# wifi-module.net
KiCad netlist of a schematic drawn in Altium Designer
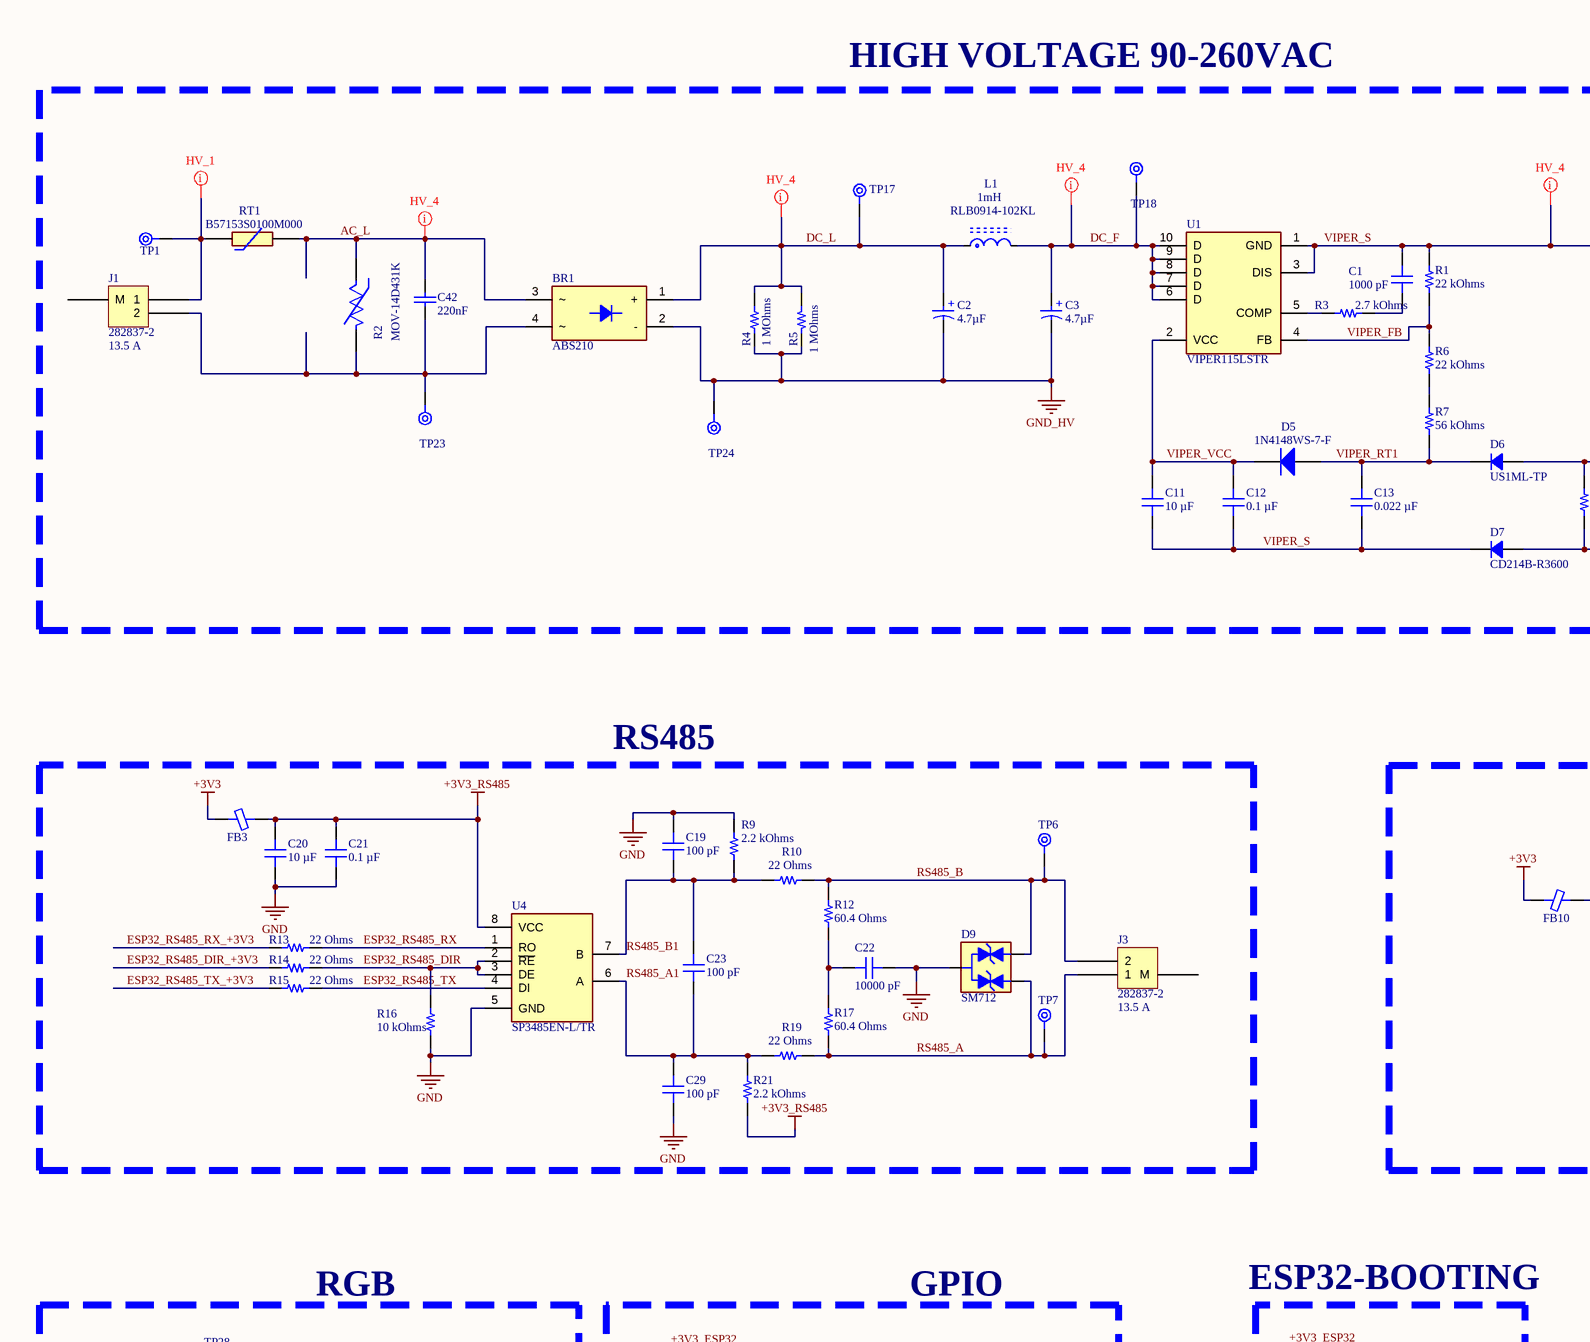
[diagram p0: wifi-module.SchDoc, top left]
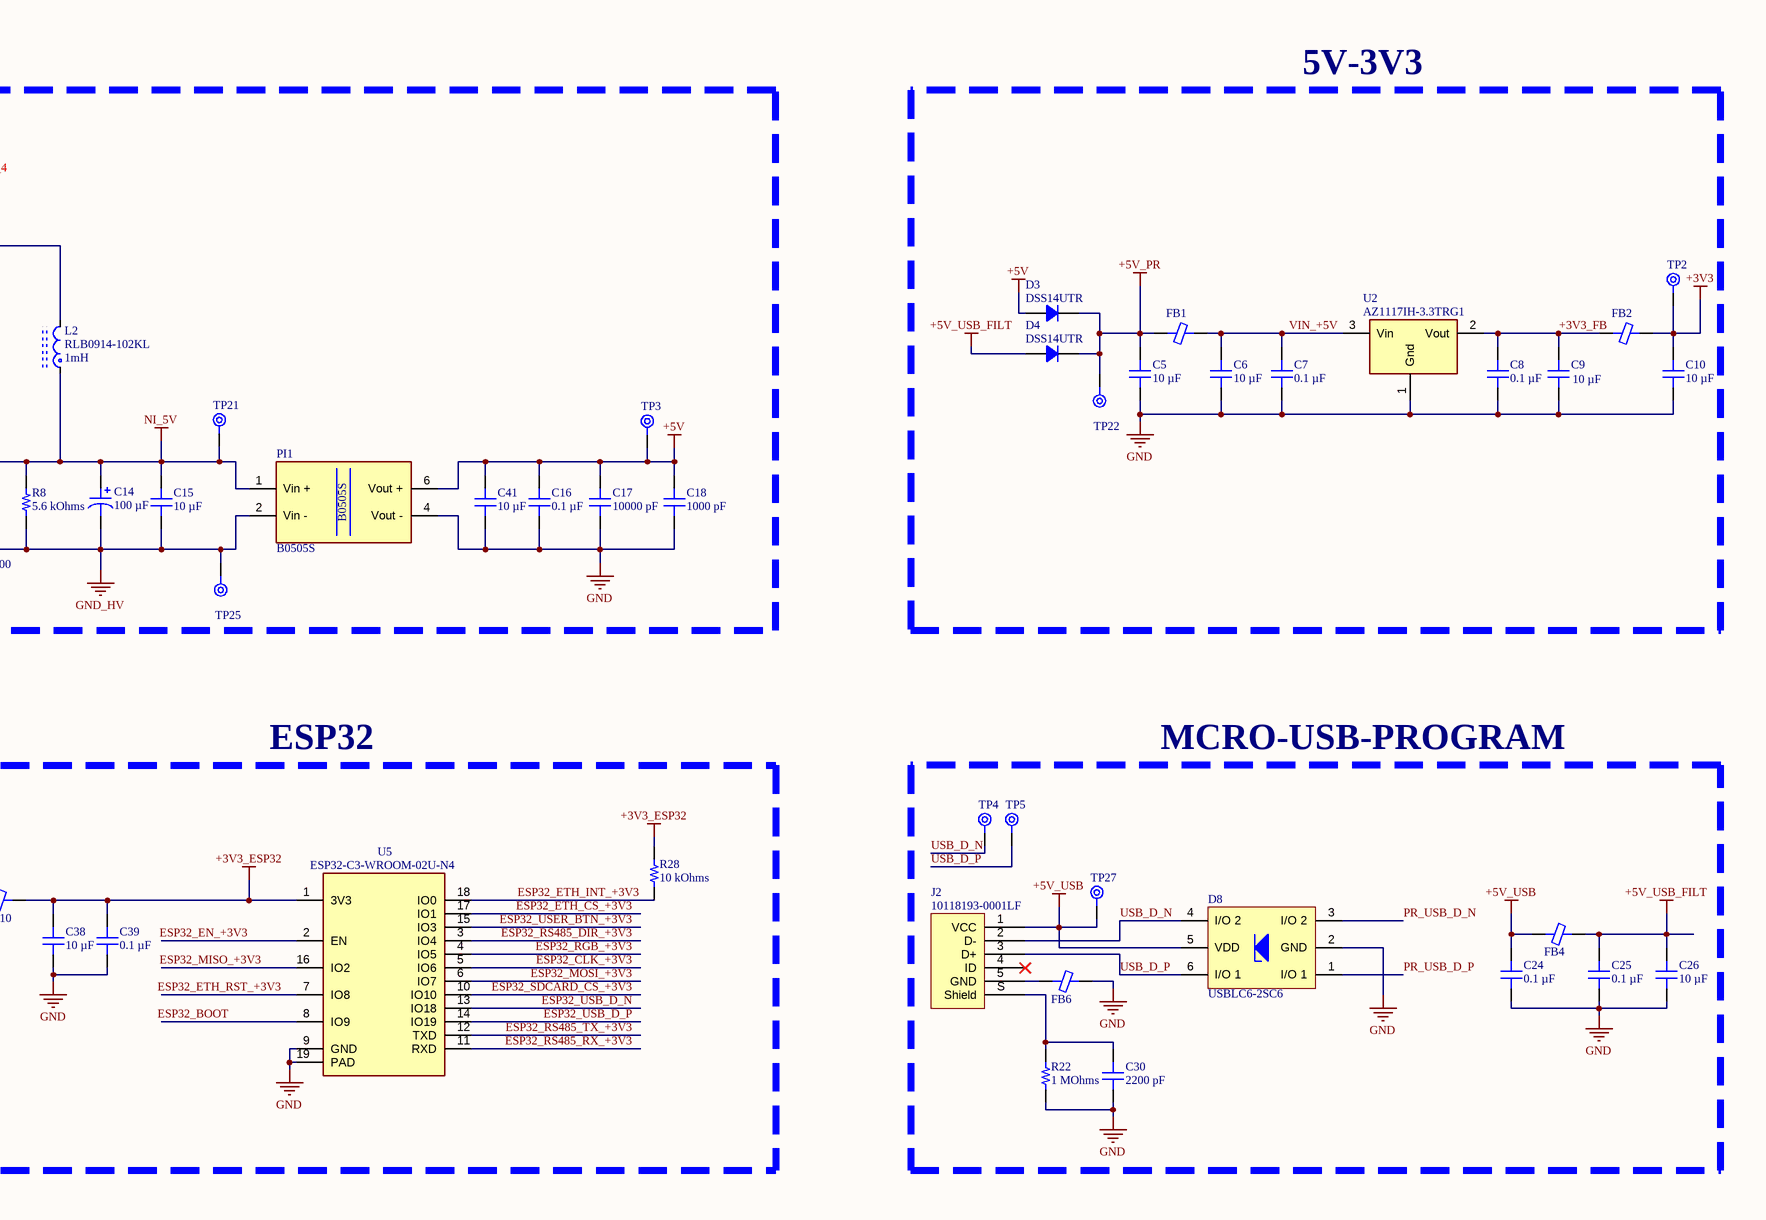
[diagram p1: wifi-module.SchDoc, top right]
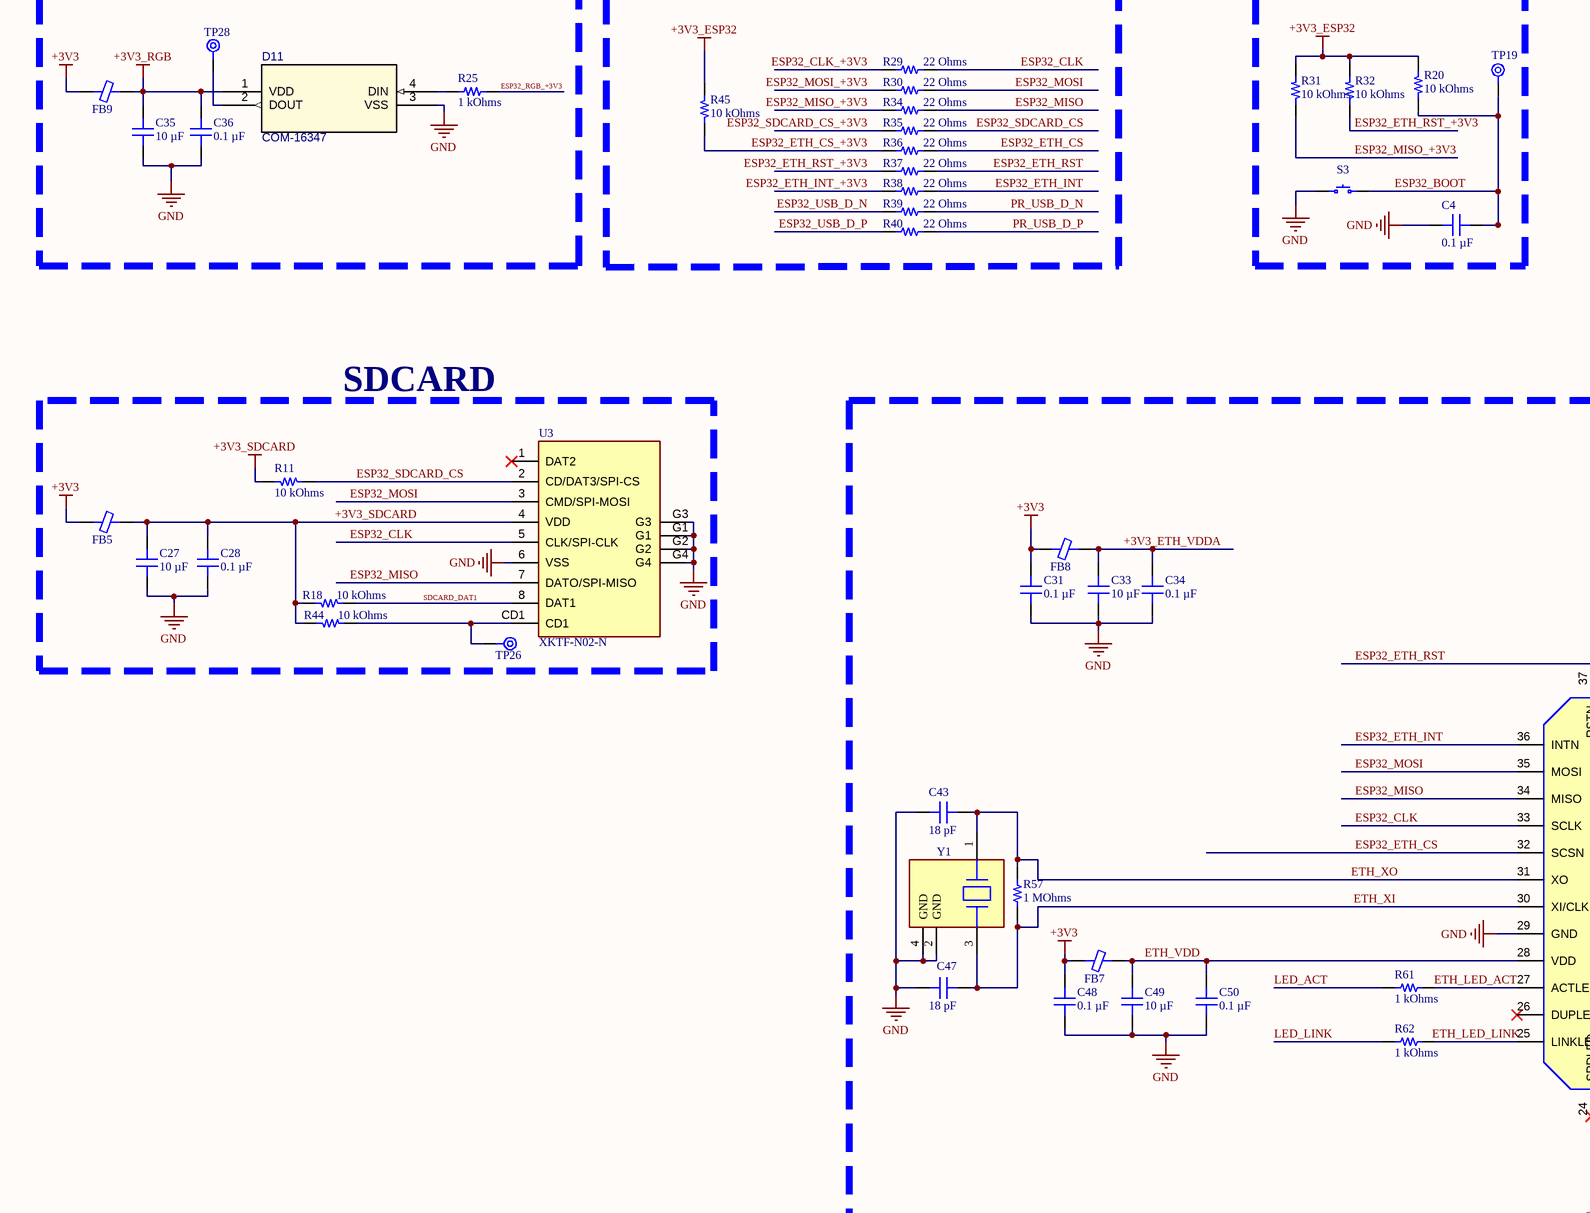
[diagram p2: wifi-module.SchDoc, bottom left]
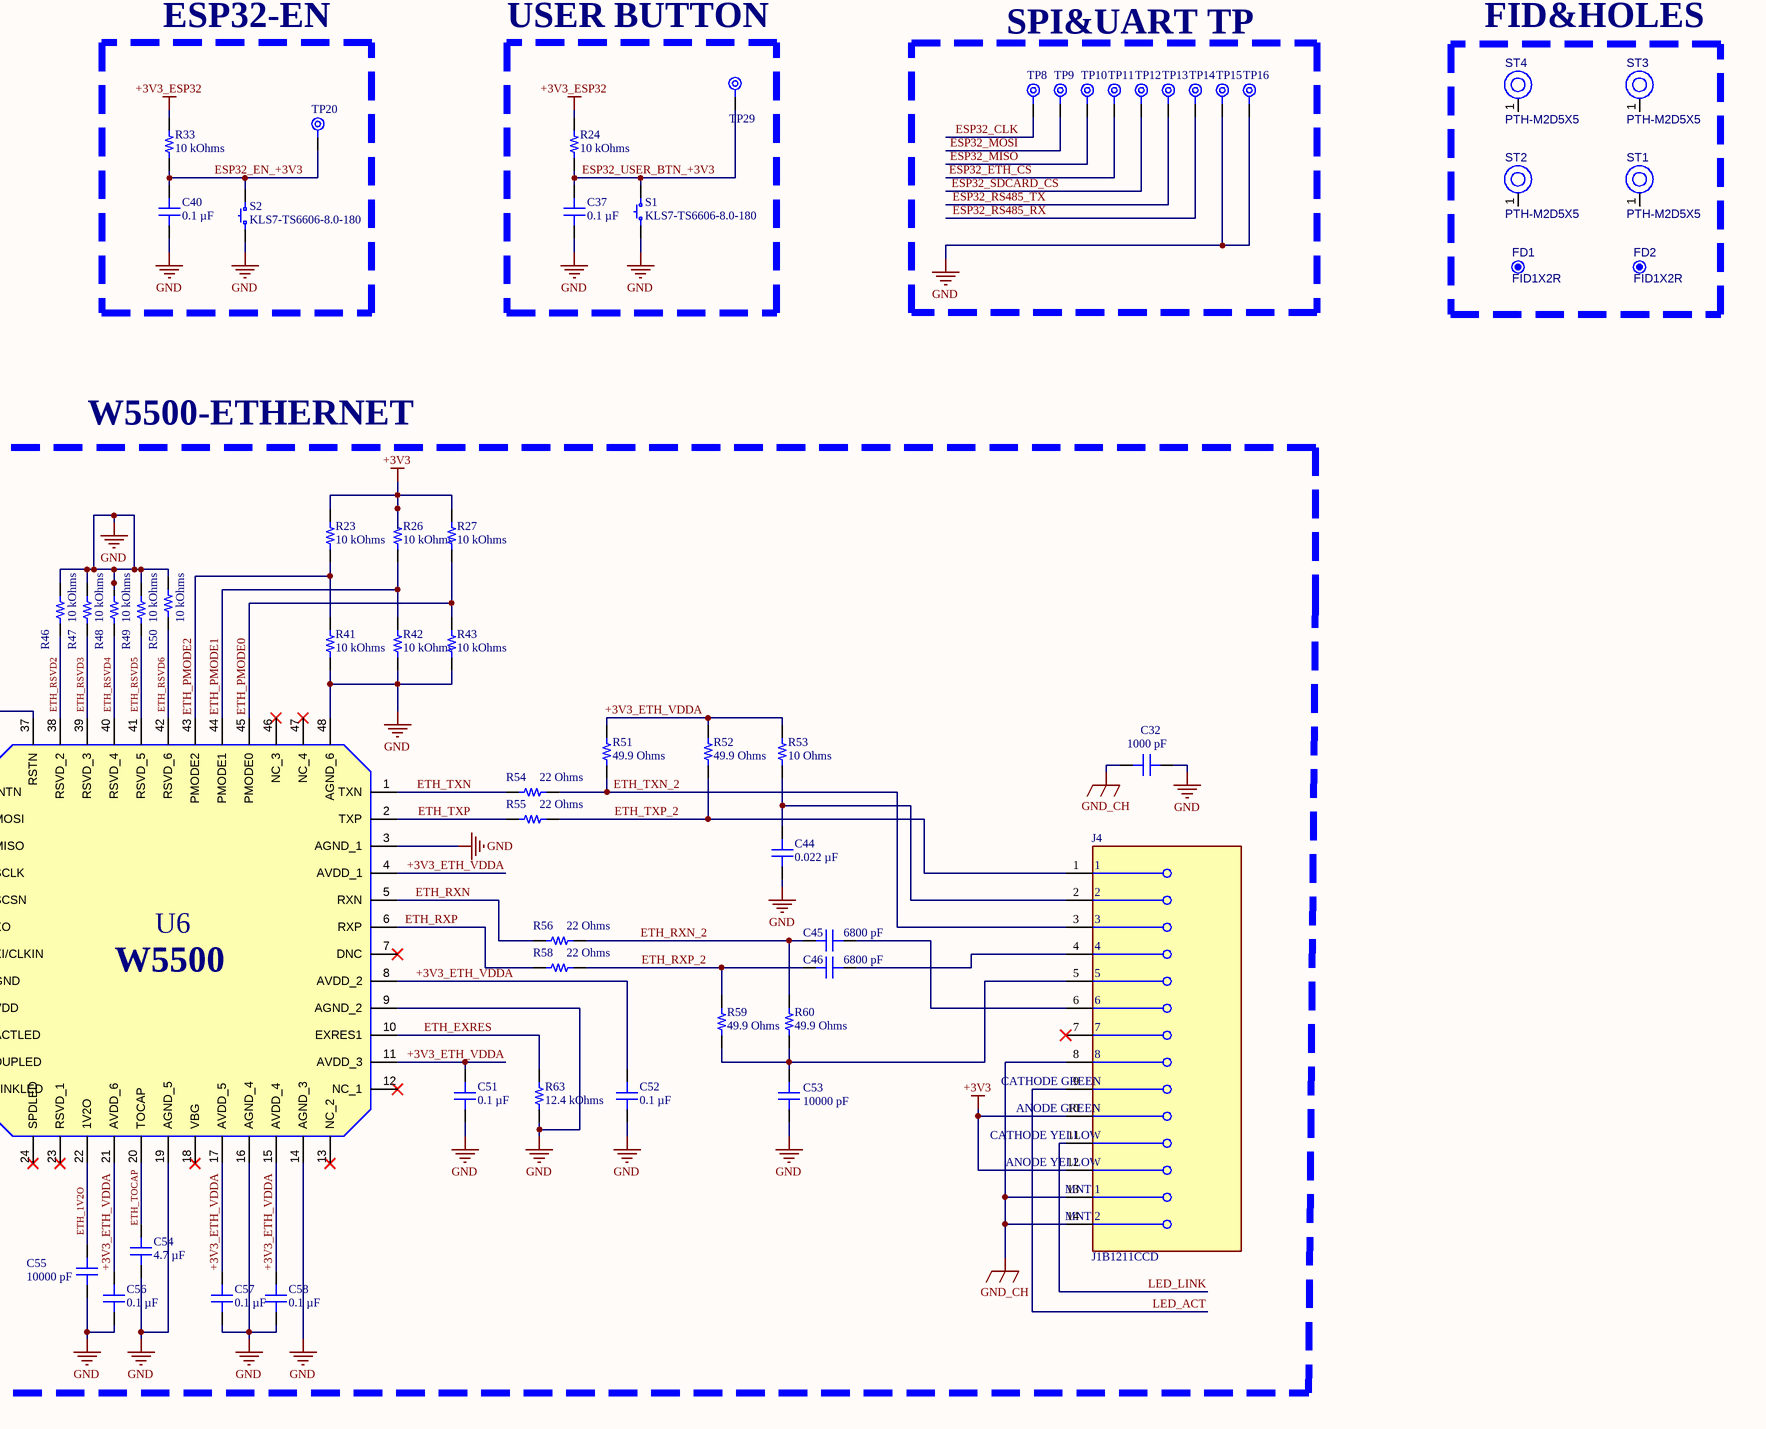
[diagram p3: wifi-module.SchDoc, bottom right]

(export (version "E")
  (design (tool "Eeschema 10.0.6"))
  (components
    (comp (ref "BR1")
      (value "ABS210")
      (footprint "SamacSys:SOP400P630X160-4N")
      (description "Bridge Rectifier")
      (libsource (lib "wifi-module-v02") (part "ABS210"))
    )
    (comp (ref "C1")
      (value "1000 pF")
      (footprint "CAP 0603_1608")
      (description "CAP CER 1000PF 50V X7R 0603")
      (fields (field (name "TOLERANCE") "±10%") (field (name "PART NUMBER") "C0603C102K5RACAUTO7411"))
      (libsource (lib "Dannie Main") (part "CAPACITOR"))
    )
    (comp (ref "C2")
      (value "4.7µF")
      (footprint "WCAP-ATG8_D8H11.5")
      (description "WCAP-ATG8 Aluminum Electrolytic Capacitor, Radial, THT, D8 x H11.5mm, 4.7uF, 400V")
      (fields
        (field (name "MANUFACTURER PART NUMBER") "860011374005")
        (field (name "MANUFACTURER") "Wurth Elektronik")
      )
      (libsource (lib "Dannie Main") (part "Capacitor_Polarized"))
    )
    (comp (ref "C3")
      (value "4.7µF")
      (footprint "WCAP-ATG8_D8H11.5")
      (description "WCAP-ATG8 Aluminum Electrolytic Capacitor, Radial, THT, D8 x H11.5mm, 4.7uF, 400V")
      (fields
        (field (name "MANUFACTURER PART NUMBER") "860011374005")
        (field (name "MANUFACTURER") "Wurth Elektronik")
      )
      (libsource (lib "Dannie Main") (part "Capacitor_Polarized"))
    )
    (comp (ref "C4")
      (value "0.1 µF")
      (footprint "CAP 0603_1608")
      (description "CAP CER 0.1UF 50V X7R 0603")
      (fields (field (name "MANUFACTURER") "Yageo") (field (name "PART NUMBER") "CC0603JRX7R9BB104"))
      (libsource (lib "Dannie Main") (part "CAPACITOR"))
    )
    (comp (ref "C5")
      (value "10 µF")
      (footprint "CAP 0805_2012")
      (description "CAP CER 10UF 25V X5R 0805")
      (fields
        (field (name "PART NUMBER") "CL21A106KAYNNNE")
        (field (name "MANUFACTURER") "Samsung Electro-Mechanics")
      )
      (libsource (lib "Dannie Main") (part "CAPACITOR"))
    )
    (comp (ref "C6")
      (value "10 µF")
      (footprint "CAP 0805_2012")
      (description "CAP CER 10UF 25V X5R 0805")
      (fields
        (field (name "PART NUMBER") "CL21A106KAYNNNE")
        (field (name "MANUFACTURER") "Samsung Electro-Mechanics")
      )
      (libsource (lib "Dannie Main") (part "CAPACITOR"))
    )
    (comp (ref "C7")
      (value "0.1 µF")
      (footprint "CAP 0603_1608")
      (description "CAP CER 0.1UF 50V X7R 0603")
      (fields (field (name "MANUFACTURER") "Yageo") (field (name "PART NUMBER") "CC0603JRX7R9BB104"))
      (libsource (lib "Dannie Main") (part "CAPACITOR"))
    )
    (comp (ref "C8")
      (value "0.1 µF")
      (footprint "CAP 0603_1608")
      (description "CAP CER 0.1UF 50V X7R 0603")
      (fields (field (name "MANUFACTURER") "Yageo") (field (name "PART NUMBER") "CC0603JRX7R9BB104"))
      (libsource (lib "Dannie Main") (part "CAPACITOR"))
    )
    (comp (ref "C9")
      (value "10 µF")
      (footprint "CAP 0805_2012")
      (description "CAP CER 10UF 25V X5R 0805")
      (fields
        (field (name "PART NUMBER") "CL21A106KAYNNNE")
        (field (name "MANUFACTURER") "Samsung Electro-Mechanics")
      )
      (libsource (lib "Dannie Main") (part "CAPACITOR"))
    )
    (comp (ref "C10")
      (value "10 µF")
      (footprint "CAP 0805_2012")
      (description "CAP CER 10UF 25V X5R 0805")
      (fields
        (field (name "PART NUMBER") "CL21A106KAYNNNE")
        (field (name "MANUFACTURER") "Samsung Electro-Mechanics")
      )
      (libsource (lib "Dannie Main") (part "CAPACITOR"))
    )
    (comp (ref "C11")
      (value "10 µF")
      (footprint "CAP 0805_2012")
      (description "CAP CER 10UF 25V X5R 0805")
      (fields
        (field (name "PART NUMBER") "CL21A106KAYNNNE")
        (field (name "MANUFACTURER") "Samsung Electro-Mechanics")
      )
      (libsource (lib "Dannie Main") (part "CAPACITOR"))
    )
    (comp (ref "C12")
      (value "0.1 µF")
      (footprint "CAP 0603_1608")
      (description "CAP CER 0.1UF 50V X7R 0603")
      (fields (field (name "MANUFACTURER") "Yageo") (field (name "PART NUMBER") "CC0603JRX7R9BB104"))
      (libsource (lib "Dannie Main") (part "CAPACITOR"))
    )
    (comp (ref "C13")
      (value "0.022 µF")
      (footprint "CAP 0603_1608")
      (description "CAP CER 0.022UF 50V X7R 0603")
      (fields (field (name "MANUFACTURER") "Samsung Electro-Mechanics") (field (name "TOLERANCE") "±10%"))
      (libsource (lib "Dannie Main") (part "CAPACITOR"))
    )
    (comp (ref "C14")
      (value "100 µF")
      (footprint "CAP ALSMD POLY 8.3MM H6.0MM")
      (description "CAP ALUM POLY 100UF 20% 35V SMD")
      (fields (field (name "MANUFACTURER") "KEMET") (field (name "TOLERANCE") "±20%"))
      (libsource (lib "Dannie Main") (part "POLARISED CAPACITOR"))
    )
    (comp (ref "C15")
      (value "10 µF")
      (footprint "CAP 0805_2012")
      (description "CAP CER 10UF 25V X5R 0805")
      (fields
        (field (name "PART NUMBER") "CL21A106KAYNNNE")
        (field (name "MANUFACTURER") "Samsung Electro-Mechanics")
      )
      (libsource (lib "Dannie Main") (part "CAPACITOR"))
    )
    (comp (ref "C16")
      (value "0.1 µF")
      (footprint "CAP 0603_1608")
      (description "CAP CER 0.1UF 50V X7R 0603")
      (fields (field (name "MANUFACTURER") "Yageo") (field (name "PART NUMBER") "CC0603JRX7R9BB104"))
      (libsource (lib "Dannie Main") (part "CAPACITOR"))
    )
    (comp (ref "C17")
      (value "10000 pF")
      (footprint "CAP 0603_1608")
      (description "CAP CER 10000PF 50V X7R 0603")
      (fields (field (name "TOLERANCE") "±10%") (field (name "PART NUMBER") "CL10B103KB8NNNC"))
      (libsource (lib "Dannie Main") (part "CAPACITOR"))
    )
    (comp (ref "C18")
      (value "1000 pF")
      (footprint "CAP 0603_1608")
      (description "CAP CER 1000PF 50V X7R 0603")
      (fields (field (name "TOLERANCE") "±10%") (field (name "PART NUMBER") "C0603C102K5RACAUTO7411"))
      (libsource (lib "Dannie Main") (part "CAPACITOR"))
    )
    (comp (ref "C19")
      (value "100 pF")
      (footprint "CAP 0603_1608")
      (description "CAP CER 100PF 50V C0G/NP0 0603")
      (fields (field (name "TOLERANCE") "±5%") (field (name "MANUFACTURER") "Samsung Electro-Mechanics"))
      (libsource (lib "Dannie Main") (part "CAPACITOR"))
    )
    (comp (ref "C20")
      (value "10 µF")
      (footprint "CAP 0603_1608")
      (description "CAP CER 10UF 6.3V X5R 0603")
      (fields (field (name "TOLERANCE") "±20%") (field (name "MANUFACTURER") "Samsung Electro-Mechanics"))
      (libsource (lib "Dannie Main") (part "CAPACITOR"))
    )
    (comp (ref "C21")
      (value "0.1 µF")
      (footprint "CAP 0603_1608")
      (description "CAP CER 0.1UF 50V X7R 0603")
      (fields (field (name "MANUFACTURER") "Yageo") (field (name "PART NUMBER") "CC0603JRX7R9BB104"))
      (libsource (lib "Dannie Main") (part "CAPACITOR"))
    )
    (comp (ref "C22")
      (value "10000 pF")
      (footprint "CAP 0603_1608")
      (description "CAP CER 10000PF 50V X7R 0603")
      (fields (field (name "TOLERANCE") "±10%") (field (name "PART NUMBER") "CL10B103KB8NNNC"))
      (libsource (lib "Dannie Main") (part "CAPACITOR"))
    )
    (comp (ref "C23")
      (value "100 pF")
      (footprint "CAP 0603_1608")
      (description "CAP CER 100PF 50V C0G/NP0 0603")
      (fields (field (name "TOLERANCE") "±5%") (field (name "MANUFACTURER") "Samsung Electro-Mechanics"))
      (libsource (lib "Dannie Main") (part "CAPACITOR"))
    )
    (comp (ref "C24")
      (value "0.1 µF")
      (footprint "CAP 0603_1608")
      (description "CAP CER 0.1UF 50V X7R 0603")
      (fields (field (name "MANUFACTURER") "Yageo") (field (name "PART NUMBER") "CC0603JRX7R9BB104"))
      (libsource (lib "Dannie Main") (part "CAPACITOR"))
    )
    (comp (ref "C25")
      (value "0.1 µF")
      (footprint "CAP 0603_1608")
      (description "CAP CER 0.1UF 50V X7R 0603")
      (fields (field (name "MANUFACTURER") "Yageo") (field (name "PART NUMBER") "CC0603JRX7R9BB104"))
      (libsource (lib "Dannie Main") (part "CAPACITOR"))
    )
    (comp (ref "C26")
      (value "10 µF")
      (footprint "CAP 0805_2012")
      (description "CAP CER 10UF 25V X5R 0805")
      (fields
        (field (name "PART NUMBER") "CL21A106KAYNNNE")
        (field (name "MANUFACTURER") "Samsung Electro-Mechanics")
      )
      (libsource (lib "Dannie Main") (part "CAPACITOR"))
    )
    (comp (ref "C27")
      (value "10 µF")
      (footprint "CAP 0603_1608")
      (description "CAP CER 10UF 6.3V X5R 0603")
      (fields (field (name "TOLERANCE") "±20%") (field (name "MANUFACTURER") "Samsung Electro-Mechanics"))
      (libsource (lib "Dannie Main") (part "CAPACITOR"))
    )
    (comp (ref "C28")
      (value "0.1 µF")
      (footprint "CAP 0603_1608")
      (description "CAP CER 0.1UF 50V X7R 0603")
      (fields (field (name "MANUFACTURER") "Yageo") (field (name "PART NUMBER") "CC0603JRX7R9BB104"))
      (libsource (lib "Dannie Main") (part "CAPACITOR"))
    )
    (comp (ref "C29")
      (value "100 pF")
      (footprint "CAP 0603_1608")
      (description "CAP CER 100PF 50V C0G/NP0 0603")
      (fields (field (name "TOLERANCE") "±5%") (field (name "MANUFACTURER") "Samsung Electro-Mechanics"))
      (libsource (lib "Dannie Main") (part "CAPACITOR"))
    )
    (comp (ref "C30")
      (value "2200 pF")
      (footprint "CAP 1206_3216 - 0.8MM")
      (description "CAP CER 2200PF 2KV X7R 1206")
      (fields (field (name "MANUFACTURER") "KEMET") (field (name "TOLERANCE") "±10%"))
      (libsource (lib "Dannie Main") (part "CAPACITOR"))
    )
    (comp (ref "C31")
      (value "0.1 µF")
      (footprint "CAP 0603_1608")
      (description "CAP CER 0.1UF 50V X7R 0603")
      (fields (field (name "MANUFACTURER") "Yageo") (field (name "PART NUMBER") "CC0603JRX7R9BB104"))
      (libsource (lib "Dannie Main") (part "CAPACITOR"))
    )
    (comp (ref "C32")
      (value "1000 pF")
      (footprint "CAP 1206_3216 - 0.8MM")
      (description "CAP CER 1000PF 2KV X7R 1206")
      (fields (field (name "TOLERANCE") "±10%") (field (name "MANUFACTURER") "Johanson Dielectrics Inc."))
      (libsource (lib "Dannie Main") (part "CAPACITOR"))
    )
    (comp (ref "C33")
      (value "10 µF")
      (footprint "CAP 0603_1608")
      (description "CAP CER 10UF 6.3V X5R 0603")
      (fields (field (name "TOLERANCE") "±20%") (field (name "MANUFACTURER") "Samsung Electro-Mechanics"))
      (libsource (lib "Dannie Main") (part "CAPACITOR"))
    )
    (comp (ref "C34")
      (value "0.1 µF")
      (footprint "CAP 0603_1608")
      (description "CAP CER 0.1UF 50V X7R 0603")
      (fields (field (name "MANUFACTURER") "Yageo") (field (name "PART NUMBER") "CC0603JRX7R9BB104"))
      (libsource (lib "Dannie Main") (part "CAPACITOR"))
    )
    (comp (ref "C35")
      (value "10 µF")
      (footprint "CAP 0603_1608")
      (description "CAP CER 10UF 6.3V X5R 0603")
      (fields (field (name "TOLERANCE") "±20%") (field (name "MANUFACTURER") "Samsung Electro-Mechanics"))
      (libsource (lib "Dannie Main") (part "CAPACITOR"))
    )
    (comp (ref "C36")
      (value "0.1 µF")
      (footprint "CAP 0603_1608")
      (description "CAP CER 0.1UF 50V X7R 0603")
      (fields (field (name "MANUFACTURER") "Yageo") (field (name "PART NUMBER") "CC0603JRX7R9BB104"))
      (libsource (lib "Dannie Main") (part "CAPACITOR"))
    )
    (comp (ref "C37")
      (value "0.1 µF")
      (footprint "CAP 0603_1608")
      (description "CAP CER 0.1UF 50V X7R 0603")
      (fields (field (name "MANUFACTURER") "Yageo") (field (name "PART NUMBER") "CC0603JRX7R9BB104"))
      (libsource (lib "Dannie Main") (part "CAPACITOR"))
    )
    (comp (ref "C38")
      (value "10 µF")
      (footprint "CAP 0603_1608")
      (description "CAP CER 10UF 6.3V X5R 0603")
      (fields (field (name "TOLERANCE") "±20%") (field (name "MANUFACTURER") "Samsung Electro-Mechanics"))
      (libsource (lib "Dannie Main") (part "CAPACITOR"))
    )
    (comp (ref "C39")
      (value "0.1 µF")
      (footprint "CAP 0603_1608")
      (description "CAP CER 0.1UF 50V X7R 0603")
      (fields (field (name "MANUFACTURER") "Yageo") (field (name "PART NUMBER") "CC0603JRX7R9BB104"))
      (libsource (lib "Dannie Main") (part "CAPACITOR"))
    )
    (comp (ref "C40")
      (value "0.1 µF")
      (footprint "CAP 0603_1608")
      (description "CAP CER 0.1UF 50V X7R 0603")
      (fields (field (name "MANUFACTURER") "Yageo") (field (name "PART NUMBER") "CC0603JRX7R9BB104"))
      (libsource (lib "Dannie Main") (part "CAPACITOR"))
    )
    (comp (ref "C41")
      (value "10 µF")
      (footprint "CAP 0805_2012")
      (description "CAP CER 10UF 25V X5R 0805")
      (fields
        (field (name "PART NUMBER") "CL21A106KAYNNNE")
        (field (name "MANUFACTURER") "Samsung Electro-Mechanics")
      )
      (libsource (lib "Dannie Main") (part "CAPACITOR"))
    )
    (comp (ref "C42")
      (value "220nF")
      (footprint "WCAP-FTX2_L15W7H12.5")
      (description "WCAP-FTX2 Film Capacitor, THT, L15 x W7 x H12.5mm, 220nF, 275V")
      (fields
        (field (name "MANUFACTURER") "Wurth Elektronik")
        (field (name "MANUFACTURER PART NUMBER") "890324024002")
      )
      (libsource (lib "Dannie Main") (part "Capacitor_Non-Polarized"))
    )
    (comp (ref "C43")
      (value "18 pF")
      (footprint "CAP 0603_1608")
      (description "CAP CER 0603 18PF 50V ULTRA STAB")
      (fields (field (name "PART NUMBER") "C0603C180K5HACAUTO") (field (name "MANUFACTURER") "KEMET"))
      (libsource (lib "Dannie Main") (part "CAPACITOR"))
    )
    (comp (ref "C44")
      (value "0.022 µF")
      (footprint "CAP 0603_1608")
      (description "CAP CER 0.022UF 50V X7R 0603")
      (fields (field (name "PART NUMBER") "C0603C223M5RACAUTO") (field (name "TOLERANCE") "±20%"))
      (libsource (lib "Dannie Main") (part "CAPACITOR"))
    )
    (comp (ref "C45")
      (value "6800 pF")
      (footprint "CAP 0603_1608")
      (description "CAP CER 6800PF 50V X7R 0603")
      (fields (field (name "PART NUMBER") "C0603C682K5RAC7411") (field (name "TOLERANCE") "±10%"))
      (libsource (lib "Dannie Main") (part "CAPACITOR"))
    )
    (comp (ref "C46")
      (value "6800 pF")
      (footprint "CAP 0603_1608")
      (description "CAP CER 6800PF 50V X7R 0603")
      (fields (field (name "PART NUMBER") "C0603C682K5RAC7411") (field (name "TOLERANCE") "±10%"))
      (libsource (lib "Dannie Main") (part "CAPACITOR"))
    )
    (comp (ref "C47")
      (value "18 pF")
      (footprint "CAP 0603_1608")
      (description "CAP CER 0603 18PF 50V ULTRA STAB")
      (fields (field (name "PART NUMBER") "C0603C180K5HACAUTO") (field (name "MANUFACTURER") "KEMET"))
      (libsource (lib "Dannie Main") (part "CAPACITOR"))
    )
    (comp (ref "C48")
      (value "0.1 µF")
      (footprint "CAP 0603_1608")
      (description "CAP CER 0.1UF 50V X7R 0603")
      (fields (field (name "MANUFACTURER") "Yageo") (field (name "PART NUMBER") "CC0603JRX7R9BB104"))
      (libsource (lib "Dannie Main") (part "CAPACITOR"))
    )
    (comp (ref "C49")
      (value "10 µF")
      (footprint "CAP 0603_1608")
      (description "CAP CER 10UF 6.3V X5R 0603")
      (fields (field (name "TOLERANCE") "±20%") (field (name "MANUFACTURER") "Samsung Electro-Mechanics"))
      (libsource (lib "Dannie Main") (part "CAPACITOR"))
    )
    (comp (ref "C50")
      (value "0.1 µF")
      (footprint "CAP 0603_1608")
      (description "CAP CER 0.1UF 50V X7R 0603")
      (fields (field (name "MANUFACTURER") "Yageo") (field (name "PART NUMBER") "CC0603JRX7R9BB104"))
      (libsource (lib "Dannie Main") (part "CAPACITOR"))
    )
    (comp (ref "C51")
      (value "0.1 µF")
      (footprint "CAP 0603_1608")
      (description "CAP CER 0.1UF 50V X7R 0603")
      (fields (field (name "MANUFACTURER") "Yageo") (field (name "PART NUMBER") "CC0603JRX7R9BB104"))
      (libsource (lib "Dannie Main") (part "CAPACITOR"))
    )
    (comp (ref "C52")
      (value "0.1 µF")
      (footprint "CAP 0603_1608")
      (description "CAP CER 0.1UF 50V X7R 0603")
      (fields (field (name "MANUFACTURER") "Yageo") (field (name "PART NUMBER") "CC0603JRX7R9BB104"))
      (libsource (lib "Dannie Main") (part "CAPACITOR"))
    )
    (comp (ref "C53")
      (value "10000 pF")
      (footprint "CAP 0603_1608")
      (description "CAP CER 10000PF 50V X7R 0603")
      (fields (field (name "TOLERANCE") "±10%") (field (name "PART NUMBER") "CL10B103KB8NNNC"))
      (libsource (lib "Dannie Main") (part "CAPACITOR"))
    )
    (comp (ref "C54")
      (value "4.7 µF")
      (footprint "CAP 1206_3216 - 0.8MM")
      (description "CAP CER 4.7UF 50V X7R 1206")
      (fields
        (field (name "PART NUMBER") "CL31B475KBHNNNE")
        (field (name "MANUFACTURER") "Samsung Electro-Mechanics")
      )
      (libsource (lib "Dannie Main") (part "CAPACITOR"))
    )
    (comp (ref "C55")
      (value "10000 pF")
      (footprint "CAP 0603_1608")
      (description "CAP CER 10000PF 50V X7R 0603")
      (fields (field (name "TOLERANCE") "±10%") (field (name "PART NUMBER") "CL10B103KB8NNNC"))
      (libsource (lib "Dannie Main") (part "CAPACITOR"))
    )
    (comp (ref "C56")
      (value "0.1 µF")
      (footprint "CAP 0603_1608")
      (description "CAP CER 0.1UF 50V X7R 0603")
      (fields (field (name "MANUFACTURER") "Yageo") (field (name "PART NUMBER") "CC0603JRX7R9BB104"))
      (libsource (lib "Dannie Main") (part "CAPACITOR"))
    )
    (comp (ref "C57")
      (value "0.1 µF")
      (footprint "CAP 0603_1608")
      (description "CAP CER 0.1UF 50V X7R 0603")
      (fields (field (name "MANUFACTURER") "Yageo") (field (name "PART NUMBER") "CC0603JRX7R9BB104"))
      (libsource (lib "Dannie Main") (part "CAPACITOR"))
    )
    (comp (ref "C58")
      (value "0.1 µF")
      (footprint "CAP 0603_1608")
      (description "CAP CER 0.1UF 50V X7R 0603")
      (fields (field (name "MANUFACTURER") "Yageo") (field (name "PART NUMBER") "CC0603JRX7R9BB104"))
      (libsource (lib "Dannie Main") (part "CAPACITOR"))
    )
    (comp (ref "D3")
      (value "DSS14UTR")
      (footprint "SOD123F")
      (description "SCHOTTKY 40V SOD-123FL")
      (fields (field (name "MANUFACTURER") "SMC Diode Solutions"))
      (libsource (lib "Dannie Main") (part "DIODE"))
    )
    (comp (ref "D4")
      (value "DSS14UTR")
      (footprint "SOD123F")
      (description "SCHOTTKY 40V SOD-123FL")
      (fields (field (name "MANUFACTURER") "SMC Diode Solutions"))
      (libsource (lib "Dannie Main") (part "DIODE"))
    )
    (comp (ref "D5")
      (value "1N4148WS-7-F")
      (footprint "DIOD-SOD323-2-A_V")
      (description "Fast Switching Diode, 75 V, 0.3 A, -65 to 150 degC, 2-Pin SOD323, RoHS, Tape and Reel")
      (fields (field (name "MANUFACTURER") "Diodes Inc"))
      (libsource (lib "Dannie Main") (part "D-AK-2"))
    )
    (comp (ref "D6")
      (value "US1ML-TP")
      (footprint "DO214AC SMA")
      (description "DIODE GEN PURP 1KV 1A DO214AC")
      (fields (field (name "MANUFACTURER") "Micro Commercial Co"))
      (libsource (lib "Dannie Main") (part "DIODE"))
    )
    (comp (ref "D7")
      (value "CD214B-R3600")
      (footprint "DO214AA SMB")
      (description "DIODE GEN PURP 600V 3A SMB")
      (fields (field (name "MANUFACTURER") "Bourns Inc."))
      (libsource (lib "Dannie Main") (part "DIODE"))
    )
    (comp (ref "D8")
      (value "USBLC6-2SC6")
      (footprint "STM-SOT23-6L_V")
      (description "Trans Voltage Suppressor Diode, 5V V(RWM), Unidirectional, 1 Element, Silicon")
      (libsource (lib "Dannie Main") (part "USBLC6-2SC6"))
    )
    (comp (ref "D9")
      (value "SM712")
      (footprint "SOT-23-3")
      (description "26V, 12V Clamp 17A (8/20µs) Ipp Tvs Diode Surface Mount SOT-23-3")
      (libsource (lib "Dannie Main") (part "SM712"))
    )
    (comp (ref "D11")
      (value "COM-16347")
      (footprint "COM-16347-Footprint-1")
      (description "Addressable Lighting - LED Serial NRZ (Shift Register) Red, Green, Blue (RGB)")
      (libsource (lib "Dannie Main") (part "COM-16347"))
    )
    (comp (ref "FB1")
      (value "MPZ1608S101ATAH0")
      (footprint "FER 0603_1608")
      (description "FERRITE BEAD 100 OHM 0603 1LN")
      (fields (field (name "MANUFACTURER") "TDK Corporation"))
      (libsource (lib "Dannie Main") (part "FERRITE CHIP"))
    )
    (comp (ref "FB2")
      (value "MPZ1608S101ATAH0")
      (footprint "FER 0603_1608")
      (description "FERRITE BEAD 100 OHM 0603 1LN")
      (fields (field (name "MANUFACTURER") "TDK Corporation"))
      (libsource (lib "Dannie Main") (part "FERRITE CHIP"))
    )
    (comp (ref "FB3")
      (value "MPZ1608S101ATAH0")
      (footprint "FER 0603_1608")
      (description "FERRITE BEAD 100 OHM 0603 1LN")
      (fields (field (name "MANUFACTURER") "TDK Corporation"))
      (libsource (lib "Dannie Main") (part "FERRITE CHIP"))
    )
    (comp (ref "FB4")
      (value "MPZ1608S101ATAH0")
      (footprint "FER 0603_1608")
      (description "FERRITE BEAD 100 OHM 0603 1LN")
      (fields (field (name "MANUFACTURER") "TDK Corporation"))
      (libsource (lib "Dannie Main") (part "FERRITE CHIP"))
    )
    (comp (ref "FB5")
      (value "MPZ1608S101ATAH0")
      (footprint "FER 0603_1608")
      (description "FERRITE BEAD 100 OHM 0603 1LN")
      (fields (field (name "MANUFACTURER") "TDK Corporation"))
      (libsource (lib "Dannie Main") (part "FERRITE CHIP"))
    )
    (comp (ref "FB6")
      (value "MPZ1608S101ATAH0")
      (footprint "FER 0603_1608")
      (description "FERRITE BEAD 100 OHM 0603 1LN")
      (fields (field (name "MANUFACTURER") "TDK Corporation"))
      (libsource (lib "Dannie Main") (part "FERRITE CHIP"))
    )
    (comp (ref "FB7")
      (value "MPZ1608S101ATAH0")
      (footprint "FER 0603_1608")
      (description "FERRITE BEAD 100 OHM 0603 1LN")
      (fields (field (name "MANUFACTURER") "TDK Corporation"))
      (libsource (lib "Dannie Main") (part "FERRITE CHIP"))
    )
    (comp (ref "FB8")
      (value "MPZ1608S101ATAH0")
      (footprint "FER 0603_1608")
      (description "FERRITE BEAD 100 OHM 0603 1LN")
      (fields (field (name "MANUFACTURER") "TDK Corporation"))
      (libsource (lib "Dannie Main") (part "FERRITE CHIP"))
    )
    (comp (ref "FB9")
      (value "MPZ1608S101ATAH0")
      (footprint "FER 0603_1608")
      (description "FERRITE BEAD 100 OHM 0603 1LN")
      (fields (field (name "MANUFACTURER") "TDK Corporation"))
      (libsource (lib "Dannie Main") (part "FERRITE CHIP"))
    )
    (comp (ref "FB10")
      (value "MPZ1608S101ATAH0")
      (footprint "FER 0603_1608")
      (description "FERRITE BEAD 100 OHM 0603 1LN")
      (fields (field (name "MANUFACTURER") "TDK Corporation"))
      (libsource (lib "Dannie Main") (part "FERRITE CHIP"))
    )
    (comp (ref "FD1")
      (value "FID1X2R")
      (footprint "FID1X2R")
      (description "Fiducial - Round 1x2mm")
      (libsource (lib "Dannie Main") (part "CMP-00134-2"))
    )
    (comp (ref "FD2")
      (value "FID1X2R")
      (footprint "FID1X2R")
      (description "Fiducial - Round 1x2mm")
      (libsource (lib "Dannie Main") (part "CMP-00134-2"))
    )
    (comp (ref "J1")
      (value "282837-2")
      (footprint "TE 282837-2")
      (description "TERM BLK 2P SIDE ENT 5.08MM PCB")
      (fields
        (field (name "VOLTAGE") "300 V")
        (field (name "CURRENT") "13.5 A")
        (field (name "MANUFACTURER") "TE Connectivity AMP Connectors")
      )
      (libsource (lib "") (part "2 PIN_1"))
    )
    (comp (ref "J2")
      (value "10118193-0001LF")
      (footprint "FCI USB 10118193-0001LF")
      (description "CONN RCPT USB2.0 MICRO B SMD R/A")
      (fields (field (name "MANUFACTURER") "Amphenol ICC (FCI)"))
      (libsource (lib "Dannie Main") (part "USB 2.0 TYPE B MICRO"))
    )
    (comp (ref "J3")
      (value "282837-2")
      (footprint "TE 282837-2")
      (description "TERM BLK 2P SIDE ENT 5.08MM PCB")
      (fields
        (field (name "VOLTAGE") "300 V")
        (field (name "CURRENT") "13.5 A")
        (field (name "MANUFACTURER") "TE Connectivity AMP Connectors")
      )
      (libsource (lib "Dannie Main") (part "2 PIN"))
    )
    (comp (ref "J4")
      (value "J1B1211CCD")
      (footprint "FP-J1B1211CCD-MFG")
      (description "CONN JACK 1PORT 100 BASE-T PCB")
      (libsource (lib "Altium Content Vault") (part "043a9053fb366fe6dc2bf5dbfb72c80"))
    )
    (comp (ref "L1")
      (value "RLB0914-102KL")
      (footprint "FP-RLB0914-MFG")
      (description "FIXED IND 1MH 420MA 2.1 OHM TH")
      (fields (field (name "INDUCTANCE") "1mH") (field (name "TOLERANCE") "10%"))
      (libsource (lib "Altium Content Vault") (part "6087e8490c250d489263be6a42f1ae3"))
    )
    (comp (ref "L2")
      (value "RLB0914-102KL")
      (footprint "FP-RLB0914-MFG")
      (description "FIXED IND 1MH 420MA 2.1 OHM TH")
      (fields (field (name "INDUCTANCE") "1mH") (field (name "TOLERANCE") "10%"))
      (libsource (lib "Altium Content Vault") (part "6087e8490c250d489263be6a42f1ae3"))
    )
    (comp (ref "PI1")
      (value "B0505S")
      (footprint "wifi-module:B0505S")
      (description "Isolated Power Modules")
      (fields (field (name "MANUFACTURER_PART_NUMBER") "B0505S-2WR3"))
      (libsource (lib "wifi-module-v02") (part "B0505S-2WR3"))
    )
    (comp (ref "R1")
      (value "22 kOhms")
      (footprint "RES 0603_1608")
      (description "RES 22K OHM 1% 1/10W 0603")
      (fields (field (name "PART NUMBER") "RC0603FR-0722KL") (field (name "MANUFACTURER") "Yageo"))
      (libsource (lib "Dannie Main") (part "RESISTOR"))
    )
    (comp (ref "R2")
      (value "MOV-14D431K")
      (footprint "FP-MOV-14D431K-MFG")
      (description "VARISTOR 430V 4.5KA DISC 14MM")
      (fields
        (field (name "MANUFACTURER") "Bourns Inc.")
        (field (name "OCTOPART") "https://octopart.com/mov-14d431k-bourns-21388914")
      )
      (libsource (lib "Altium Content Vault") (part "78a88060d5b7b043d6e48adc4284376"))
    )
    (comp (ref "R3")
      (value "2.7 kOhms")
      (footprint "RES 0603_1608")
      (description "RES 2.7K OHM 1% 1/10W 0603")
      (fields (field (name "MANUFACTURER") "Yageo") (field (name "PART NUMBER") "RC0603FR-072K7L"))
      (libsource (lib "Dannie Main") (part "RESISTOR"))
    )
    (comp (ref "R4")
      (value "1 MOhms")
      (footprint "RES 2512_6432")
      (description "RES 1M OHM 5% 1W 2512")
      (fields (field (name "PART NUMBER") "RMCF2512JT1M00") (field (name "TOLERANCE") "±5%"))
      (libsource (lib "Dannie Main") (part "RESISTOR"))
    )
    (comp (ref "R5")
      (value "1 MOhms")
      (footprint "RES 2512_6432")
      (description "RES 1M OHM 5% 1W 2512")
      (fields (field (name "PART NUMBER") "RMCF2512JT1M00") (field (name "TOLERANCE") "±5%"))
      (libsource (lib "Dannie Main") (part "RESISTOR"))
    )
    (comp (ref "R6")
      (value "22 kOhms")
      (footprint "RES 0603_1608")
      (description "RES 22K OHM 1% 1/10W 0603")
      (fields (field (name "PART NUMBER") "RC0603FR-0722KL") (field (name "MANUFACTURER") "Yageo"))
      (libsource (lib "Dannie Main") (part "RESISTOR"))
    )
    (comp (ref "R7")
      (value "56 kOhms")
      (footprint "RES 0603_1608")
      (description "RES 56K OHM 1% 1/10W 0603")
      (fields (field (name "MANUFACTURER") "Yageo") (field (name "PART NUMBER") "RC0603FR-0756KL"))
      (libsource (lib "Dannie Main") (part "RESISTOR"))
    )
    (comp (ref "R8")
      (value "5.6 kOhms")
      (footprint "RES 0603_1608")
      (description "RES 5.6K OHM 1% 1/10W 0603")
      (fields (field (name "TOLERANCE") "±1%") (field (name "MANUFACTURER") "Yageo"))
      (libsource (lib "Dannie Main") (part "RESISTOR"))
    )
    (comp (ref "R9")
      (value "2.2 kOhms")
      (footprint "RES 0603_1608")
      (description "RES 2.2K OHM 1% 1/10W 0603")
      (fields (field (name "TOLERANCE") "±1%") (field (name "PART NUMBER") "RC0603FR-072K2L"))
      (libsource (lib "Dannie Main") (part "RESISTOR"))
    )
    (comp (ref "R10")
      (value "22 Ohms")
      (footprint "RES 0603_1608")
      (description "RES 22 OHM 1% 1/10W 0603")
      (fields (field (name "MANUFACTURER") "Yageo") (field (name "TOLERANCE") "±1%"))
      (libsource (lib "Dannie Main") (part "RESISTOR"))
    )
    (comp (ref "R11")
      (value "10 kOhms")
      (footprint "RES 0603_1608")
      (description "RES 10K OHM 1% 1/10W 0603")
      (fields (field (name "PART NUMBER") "RC0603FR-0710KL") (field (name "TOLERANCE") "±1%"))
      (libsource (lib "Dannie Main") (part "RESISTOR"))
    )
    (comp (ref "R12")
      (value "60.4 Ohms")
      (footprint "RES 0603_1608")
      (description "RES 60.4 OHM 1% 1/10W 0603")
      (fields (field (name "TOLERANCE") "±1%") (field (name "MANUFACTURER") "Yageo"))
      (libsource (lib "Dannie Main") (part "RESISTOR"))
    )
    (comp (ref "R13")
      (value "22 Ohms")
      (footprint "RES 0603_1608")
      (description "RES 22 OHM 1% 1/10W 0603")
      (fields (field (name "MANUFACTURER") "Yageo") (field (name "TOLERANCE") "±1%"))
      (libsource (lib "Dannie Main") (part "RESISTOR"))
    )
    (comp (ref "R14")
      (value "22 Ohms")
      (footprint "RES 0603_1608")
      (description "RES 22 OHM 1% 1/10W 0603")
      (fields (field (name "MANUFACTURER") "Yageo") (field (name "TOLERANCE") "±1%"))
      (libsource (lib "Dannie Main") (part "RESISTOR"))
    )
    (comp (ref "R15")
      (value "22 Ohms")
      (footprint "RES 0603_1608")
      (description "RES 22 OHM 1% 1/10W 0603")
      (fields (field (name "MANUFACTURER") "Yageo") (field (name "TOLERANCE") "±1%"))
      (libsource (lib "Dannie Main") (part "RESISTOR"))
    )
    (comp (ref "R16")
      (value "10 kOhms")
      (footprint "RES 0603_1608")
      (description "RES 10K OHM 1% 1/10W 0603")
      (fields (field (name "PART NUMBER") "RC0603FR-0710KL") (field (name "TOLERANCE") "±1%"))
      (libsource (lib "Dannie Main") (part "RESISTOR"))
    )
    (comp (ref "R17")
      (value "60.4 Ohms")
      (footprint "RES 0603_1608")
      (description "RES 60.4 OHM 1% 1/10W 0603")
      (fields (field (name "TOLERANCE") "±1%") (field (name "MANUFACTURER") "Yageo"))
      (libsource (lib "Dannie Main") (part "RESISTOR"))
    )
    (comp (ref "R18")
      (value "10 kOhms")
      (footprint "RES 0603_1608")
      (description "RES 10K OHM 1% 1/10W 0603")
      (fields (field (name "PART NUMBER") "RC0603FR-0710KL") (field (name "TOLERANCE") "±1%"))
      (libsource (lib "Dannie Main") (part "RESISTOR"))
    )
    (comp (ref "R19")
      (value "22 Ohms")
      (footprint "RES 0603_1608")
      (description "RES 22 OHM 1% 1/10W 0603")
      (fields (field (name "MANUFACTURER") "Yageo") (field (name "TOLERANCE") "±1%"))
      (libsource (lib "Dannie Main") (part "RESISTOR"))
    )
    (comp (ref "R20")
      (value "10 kOhms")
      (footprint "RES 0603_1608")
      (description "RES 10K OHM 1% 1/10W 0603")
      (fields (field (name "PART NUMBER") "RC0603FR-0710KL") (field (name "TOLERANCE") "±1%"))
      (libsource (lib "Dannie Main") (part "RESISTOR"))
    )
    (comp (ref "R21")
      (value "2.2 kOhms")
      (footprint "RES 0603_1608")
      (description "RES 2.2K OHM 1% 1/10W 0603")
      (fields (field (name "TOLERANCE") "±1%") (field (name "PART NUMBER") "RC0603FR-072K2L"))
      (libsource (lib "Dannie Main") (part "RESISTOR"))
    )
    (comp (ref "R22")
      (value "1 MOhms")
      (footprint "RES 1206_3216")
      (description "RES 1M OHM 1% 1/4W 1206")
      (fields (field (name "TOLERANCE") "±1%") (field (name "PART NUMBER") "RC1206FR-071ML"))
      (libsource (lib "Dannie Main") (part "RESISTOR"))
    )
    (comp (ref "R23")
      (value "10 kOhms")
      (footprint "RES 0603_1608")
      (description "RES 10K OHM 1% 1/10W 0603")
      (fields (field (name "PART NUMBER") "RC0603FR-0710KL") (field (name "TOLERANCE") "±1%"))
      (libsource (lib "Dannie Main") (part "RESISTOR"))
    )
    (comp (ref "R24")
      (value "10 kOhms")
      (footprint "RES 0603_1608")
      (description "RES 10K OHM 1% 1/10W 0603")
      (fields (field (name "PART NUMBER") "RC0603FR-0710KL") (field (name "TOLERANCE") "±1%"))
      (libsource (lib "Dannie Main") (part "RESISTOR"))
    )
    (comp (ref "R25")
      (value "1 kOhms")
      (footprint "RES 0603_1608")
      (description "RES 1K OHM 1% 1/10W 0603")
      (fields (field (name "PART NUMBER") "RC0603FR-071KL") (field (name "TOLERANCE") "±1%"))
      (libsource (lib "Dannie Main") (part "RESISTOR"))
    )
    (comp (ref "R26")
      (value "10 kOhms")
      (footprint "RES 0603_1608")
      (description "RES 10K OHM 1% 1/10W 0603")
      (fields (field (name "PART NUMBER") "RC0603FR-0710KL") (field (name "TOLERANCE") "±1%"))
      (libsource (lib "Dannie Main") (part "RESISTOR"))
    )
    (comp (ref "R27")
      (value "10 kOhms")
      (footprint "RES 0603_1608")
      (description "RES 10K OHM 1% 1/10W 0603")
      (fields (field (name "PART NUMBER") "RC0603FR-0710KL") (field (name "TOLERANCE") "±1%"))
      (libsource (lib "Dannie Main") (part "RESISTOR"))
    )
    (comp (ref "R28")
      (value "10 kOhms")
      (footprint "RES 0603_1608")
      (description "RES 10K OHM 1% 1/10W 0603")
      (fields (field (name "PART NUMBER") "RC0603FR-0710KL") (field (name "TOLERANCE") "±1%"))
      (libsource (lib "Dannie Main") (part "RESISTOR"))
    )
    (comp (ref "R29")
      (value "22 Ohms")
      (footprint "RES 0603_1608")
      (description "RES 22 OHM 1% 1/10W 0603")
      (fields (field (name "MANUFACTURER") "Yageo") (field (name "TOLERANCE") "±1%"))
      (libsource (lib "Dannie Main") (part "RESISTOR"))
    )
    (comp (ref "R30")
      (value "22 Ohms")
      (footprint "RES 0603_1608")
      (description "RES 22 OHM 1% 1/10W 0603")
      (fields (field (name "MANUFACTURER") "Yageo") (field (name "TOLERANCE") "±1%"))
      (libsource (lib "Dannie Main") (part "RESISTOR"))
    )
    (comp (ref "R31")
      (value "10 kOhms")
      (footprint "RES 0603_1608")
      (description "RES 10K OHM 1% 1/10W 0603")
      (fields (field (name "PART NUMBER") "RC0603FR-0710KL") (field (name "TOLERANCE") "±1%"))
      (libsource (lib "Dannie Main") (part "RESISTOR"))
    )
    (comp (ref "R32")
      (value "10 kOhms")
      (footprint "RES 0603_1608")
      (description "RES 10K OHM 1% 1/10W 0603")
      (fields (field (name "PART NUMBER") "RC0603FR-0710KL") (field (name "TOLERANCE") "±1%"))
      (libsource (lib "Dannie Main") (part "RESISTOR"))
    )
    (comp (ref "R33")
      (value "10 kOhms")
      (footprint "RES 0603_1608")
      (description "RES 10K OHM 1% 1/10W 0603")
      (fields (field (name "PART NUMBER") "RC0603FR-0710KL") (field (name "TOLERANCE") "±1%"))
      (libsource (lib "Dannie Main") (part "RESISTOR"))
    )
    (comp (ref "R34")
      (value "22 Ohms")
      (footprint "RES 0603_1608")
      (description "RES 22 OHM 1% 1/10W 0603")
      (fields (field (name "MANUFACTURER") "Yageo") (field (name "TOLERANCE") "±1%"))
      (libsource (lib "Dannie Main") (part "RESISTOR"))
    )
    (comp (ref "R35")
      (value "22 Ohms")
      (footprint "RES 0603_1608")
      (description "RES 22 OHM 1% 1/10W 0603")
      (fields (field (name "MANUFACTURER") "Yageo") (field (name "TOLERANCE") "±1%"))
      (libsource (lib "Dannie Main") (part "RESISTOR"))
    )
    (comp (ref "R36")
      (value "22 Ohms")
      (footprint "RES 0603_1608")
      (description "RES 22 OHM 1% 1/10W 0603")
      (fields (field (name "MANUFACTURER") "Yageo") (field (name "TOLERANCE") "±1%"))
      (libsource (lib "Dannie Main") (part "RESISTOR"))
    )
    (comp (ref "R37")
      (value "22 Ohms")
      (footprint "RES 0603_1608")
      (description "RES 22 OHM 1% 1/10W 0603")
      (fields (field (name "MANUFACTURER") "Yageo") (field (name "TOLERANCE") "±1%"))
      (libsource (lib "Dannie Main") (part "RESISTOR"))
    )
    (comp (ref "R38")
      (value "22 Ohms")
      (footprint "RES 0603_1608")
      (description "RES 22 OHM 1% 1/10W 0603")
      (fields (field (name "MANUFACTURER") "Yageo") (field (name "TOLERANCE") "±1%"))
      (libsource (lib "Dannie Main") (part "RESISTOR"))
    )
    (comp (ref "R39")
      (value "22 Ohms")
      (footprint "RES 0603_1608")
      (description "RES 22 OHM 1% 1/10W 0603")
      (fields (field (name "MANUFACTURER") "Yageo") (field (name "TOLERANCE") "±1%"))
      (libsource (lib "Dannie Main") (part "RESISTOR"))
    )
    (comp (ref "R40")
      (value "22 Ohms")
      (footprint "RES 0603_1608")
      (description "RES 22 OHM 1% 1/10W 0603")
      (fields (field (name "MANUFACTURER") "Yageo") (field (name "TOLERANCE") "±1%"))
      (libsource (lib "Dannie Main") (part "RESISTOR"))
    )
    (comp (ref "R41")
      (value "10 kOhms")
      (footprint "RES 0603_1608")
      (description "RES 10K OHM 1% 1/10W 0603")
      (fields (field (name "PART NUMBER") "RC0603FR-0710KL") (field (name "TOLERANCE") "±1%"))
      (libsource (lib "Dannie Main") (part "RESISTOR"))
    )
    (comp (ref "R42")
      (value "10 kOhms")
      (footprint "RES 0603_1608")
      (description "RES 10K OHM 1% 1/10W 0603")
      (fields (field (name "PART NUMBER") "RC0603FR-0710KL") (field (name "TOLERANCE") "±1%"))
      (libsource (lib "Dannie Main") (part "RESISTOR"))
    )
    (comp (ref "R43")
      (value "10 kOhms")
      (footprint "RES 0603_1608")
      (description "RES 10K OHM 1% 1/10W 0603")
      (fields (field (name "PART NUMBER") "RC0603FR-0710KL") (field (name "TOLERANCE") "±1%"))
      (libsource (lib "Dannie Main") (part "RESISTOR"))
    )
    (comp (ref "R44")
      (value "10 kOhms")
      (footprint "RES 0603_1608")
      (description "RES 10K OHM 1% 1/10W 0603")
      (fields (field (name "PART NUMBER") "RC0603FR-0710KL") (field (name "TOLERANCE") "±1%"))
      (libsource (lib "Dannie Main") (part "RESISTOR"))
    )
    (comp (ref "R45")
      (value "10 kOhms")
      (footprint "RES 0603_1608")
      (description "RES 10K OHM 1% 1/10W 0603")
      (fields (field (name "PART NUMBER") "RC0603FR-0710KL") (field (name "TOLERANCE") "±1%"))
      (libsource (lib "Dannie Main") (part "RESISTOR"))
    )
    (comp (ref "R46")
      (value "10 kOhms")
      (footprint "RES 0603_1608")
      (description "RES 10K OHM 1% 1/10W 0603")
      (fields (field (name "PART NUMBER") "RC0603FR-0710KL") (field (name "TOLERANCE") "±1%"))
      (libsource (lib "Dannie Main") (part "RESISTOR"))
    )
    (comp (ref "R47")
      (value "10 kOhms")
      (footprint "RES 0603_1608")
      (description "RES 10K OHM 1% 1/10W 0603")
      (fields (field (name "PART NUMBER") "RC0603FR-0710KL") (field (name "TOLERANCE") "±1%"))
      (libsource (lib "Dannie Main") (part "RESISTOR"))
    )
    (comp (ref "R48")
      (value "10 kOhms")
      (footprint "RES 0603_1608")
      (description "RES 10K OHM 1% 1/10W 0603")
      (fields (field (name "PART NUMBER") "RC0603FR-0710KL") (field (name "TOLERANCE") "±1%"))
      (libsource (lib "Dannie Main") (part "RESISTOR"))
    )
    (comp (ref "R49")
      (value "10 kOhms")
      (footprint "RES 0603_1608")
      (description "RES 10K OHM 1% 1/10W 0603")
      (fields (field (name "PART NUMBER") "RC0603FR-0710KL") (field (name "TOLERANCE") "±1%"))
      (libsource (lib "Dannie Main") (part "RESISTOR"))
    )
    (comp (ref "R50")
      (value "10 kOhms")
      (footprint "RES 0603_1608")
      (description "RES 10K OHM 1% 1/10W 0603")
      (fields (field (name "PART NUMBER") "RC0603FR-0710KL") (field (name "TOLERANCE") "±1%"))
      (libsource (lib "Dannie Main") (part "RESISTOR"))
    )
    (comp (ref "R51")
      (value "49.9 Ohms")
      (footprint "RES 0603_1608")
      (description "RES 49.9 OHM 1% 1/10W 0603")
      (fields (field (name "TOLERANCE") "±1%") (field (name "PART NUMBER") "RC0603FR-0749R9L"))
      (libsource (lib "Dannie Main") (part "RESISTOR"))
    )
    (comp (ref "R52")
      (value "49.9 Ohms")
      (footprint "RES 0603_1608")
      (description "RES 49.9 OHM 1% 1/10W 0603")
      (fields (field (name "TOLERANCE") "±1%") (field (name "PART NUMBER") "RC0603FR-0749R9L"))
      (libsource (lib "Dannie Main") (part "RESISTOR"))
    )
    (comp (ref "R53")
      (value "10 Ohms")
      (footprint "RES 0603_1608")
      (description "RES 10 OHM 1% 1/10W 0603")
      (fields (field (name "PART NUMBER") "RC0603FR-0710RL") (field (name "MANUFACTURER") "Yageo"))
      (libsource (lib "Dannie Main") (part "RESISTOR"))
    )
    (comp (ref "R54")
      (value "22 Ohms")
      (footprint "RES 0603_1608")
      (description "RES 22 OHM 1% 1/10W 0603")
      (fields (field (name "MANUFACTURER") "Yageo") (field (name "TOLERANCE") "±1%"))
      (libsource (lib "Dannie Main") (part "RESISTOR"))
    )
    (comp (ref "R55")
      (value "22 Ohms")
      (footprint "RES 0603_1608")
      (description "RES 22 OHM 1% 1/10W 0603")
      (fields (field (name "MANUFACTURER") "Yageo") (field (name "TOLERANCE") "±1%"))
      (libsource (lib "Dannie Main") (part "RESISTOR"))
    )
    (comp (ref "R56")
      (value "22 Ohms")
      (footprint "RES 0603_1608")
      (description "RES 22 OHM 1% 1/10W 0603")
      (fields (field (name "MANUFACTURER") "Yageo") (field (name "TOLERANCE") "±1%"))
      (libsource (lib "Dannie Main") (part "RESISTOR"))
    )
    (comp (ref "R57")
      (value "1 MOhms")
      (footprint "RES 0603_1608")
      (description "RES 1M OHM 1% 1/10W 0603")
      (fields (field (name "MANUFACTURER") "Yageo") (field (name "PART NUMBER") "RC0603FR-071ML"))
      (libsource (lib "Dannie Main") (part "RESISTOR"))
    )
    (comp (ref "R58")
      (value "22 Ohms")
      (footprint "RES 0603_1608")
      (description "RES 22 OHM 1% 1/10W 0603")
      (fields (field (name "MANUFACTURER") "Yageo") (field (name "TOLERANCE") "±1%"))
      (libsource (lib "Dannie Main") (part "RESISTOR"))
    )
    (comp (ref "R59")
      (value "49.9 Ohms")
      (footprint "RES 0603_1608")
      (description "RES 49.9 OHM 1% 1/10W 0603")
      (fields (field (name "TOLERANCE") "±1%") (field (name "PART NUMBER") "RC0603FR-0749R9L"))
      (libsource (lib "Dannie Main") (part "RESISTOR"))
    )
    (comp (ref "R60")
      (value "49.9 Ohms")
      (footprint "RES 0603_1608")
      (description "RES 49.9 OHM 1% 1/10W 0603")
      (fields (field (name "TOLERANCE") "±1%") (field (name "PART NUMBER") "RC0603FR-0749R9L"))
      (libsource (lib "Dannie Main") (part "RESISTOR"))
    )
    (comp (ref "R61")
      (value "1 kOhms")
      (footprint "RES 0603_1608")
      (description "RES 1K OHM 1% 1/10W 0603")
      (fields (field (name "PART NUMBER") "RC0603FR-071KL") (field (name "TOLERANCE") "±1%"))
      (libsource (lib "Dannie Main") (part "RESISTOR"))
    )
    (comp (ref "R62")
      (value "1 kOhms")
      (footprint "RES 0603_1608")
      (description "RES 1K OHM 1% 1/10W 0603")
      (fields (field (name "PART NUMBER") "RC0603FR-071KL") (field (name "TOLERANCE") "±1%"))
      (libsource (lib "Dannie Main") (part "RESISTOR"))
    )
    (comp (ref "R63")
      (value "12.4 kOhms")
      (footprint "RES 0603_1608")
      (description "RES 12.4K OHM 1% 1/10W 0603")
      (fields (field (name "TOLERANCE") "±1%") (field (name "MANUFACTURER") "Yageo"))
      (libsource (lib "Dannie Main") (part "RESISTOR"))
    )
    (comp (ref "RT1")
      (value "B57153S0100M000")
      (footprint "B57153S0100M000-Footprint-1")
      (description "Inrush Current Limiter 10 Ohms ±20% 2 A 0.335\" (8.50mm)")
      (libsource (lib "Dannie Main") (part "B57153S0100M000"))
    )
    (comp (ref "S1")
      (value "KLS7-TS6606-8.0-180")
      (footprint "KLS7TS660680180")
      (description "Switch")
      (libsource (lib "Dannie Main") (part "KLS7-TS6606-8.0-180"))
    )
    (comp (ref "S2")
      (value "KLS7-TS6606-8.0-180")
      (footprint "KLS7TS660680180")
      (description "Switch")
      (libsource (lib "Dannie Main") (part "KLS7-TS6606-8.0-180"))
    )
    (comp (ref "S3")
      (value "KLS7-TS6606-8.0-180")
      (footprint "KLS7TS660680180")
      (description "Switch")
      (libsource (lib "Dannie Main") (part "KLS7-TS6606-8.0-180"))
    )
    (comp (ref "ST1")
      (value "PTH-M2D5X5")
      (footprint "PTH-M2D5X5")
      (description "M2 PTH (2.5mm), 5mm pad")
      (libsource (lib "Dannie Main") (part "CMP-00028-00000-1"))
    )
    (comp (ref "ST2")
      (value "PTH-M2D5X5")
      (footprint "PTH-M2D5X5")
      (description "M2 PTH (2.5mm), 5mm pad")
      (libsource (lib "Dannie Main") (part "CMP-00028-00000-1"))
    )
    (comp (ref "ST3")
      (value "PTH-M2D5X5")
      (footprint "PTH-M2D5X5")
      (description "M2 PTH (2.5mm), 5mm pad")
      (libsource (lib "Dannie Main") (part "CMP-00028-00000-1"))
    )
    (comp (ref "ST4")
      (value "PTH-M2D5X5")
      (footprint "PTH-M2D5X5")
      (description "M2 PTH (2.5mm), 5mm pad")
      (libsource (lib "Dannie Main") (part "CMP-00028-00000-1"))
    )
    (comp (ref "TP1")
      (value "TPAD1200")
      (footprint "TPAD1200")
      (description "1.2mm round")
      (libsource (lib "Dannie Main") (part "TPAD1200"))
    )
    (comp (ref "TP2")
      (value "TPAD1200")
      (footprint "TPAD1200")
      (description "1.2mm round")
      (libsource (lib "Dannie Main") (part "TPAD1200"))
    )
    (comp (ref "TP3")
      (value "TPAD1200")
      (footprint "TPAD1200")
      (description "1.2mm round")
      (libsource (lib "Dannie Main") (part "TPAD1200"))
    )
    (comp (ref "TP4")
      (value "TPAD1200")
      (footprint "TPAD1200")
      (description "1.2mm round")
      (libsource (lib "Dannie Main") (part "TPAD1200"))
    )
    (comp (ref "TP5")
      (value "TPAD1200")
      (footprint "TPAD1200")
      (description "1.2mm round")
      (libsource (lib "Dannie Main") (part "TPAD1200"))
    )
    (comp (ref "TP6")
      (value "TPAD1200")
      (footprint "TPAD1200")
      (description "1.2mm round")
      (libsource (lib "Dannie Main") (part "TPAD1200"))
    )
    (comp (ref "TP7")
      (value "TPAD1200")
      (footprint "TPAD1200")
      (description "1.2mm round")
      (libsource (lib "Dannie Main") (part "TPAD1200"))
    )
    (comp (ref "TP8")
      (value "TPAD1200")
      (footprint "TPAD1200")
      (description "1.2mm round")
      (libsource (lib "Dannie Main") (part "TPAD1200"))
    )
    (comp (ref "TP9")
      (value "TPAD1200")
      (footprint "TPAD1200")
      (description "1.2mm round")
      (libsource (lib "Dannie Main") (part "TPAD1200"))
    )
    (comp (ref "TP10")
      (value "TPAD1200")
      (footprint "TPAD1200")
      (description "1.2mm round")
      (libsource (lib "Dannie Main") (part "TPAD1200"))
    )
    (comp (ref "TP11")
      (value "TPAD1200")
      (footprint "TPAD1200")
      (description "1.2mm round")
      (libsource (lib "Dannie Main") (part "TPAD1200"))
    )
    (comp (ref "TP12")
      (value "TPAD1200")
      (footprint "TPAD1200")
      (description "1.2mm round")
      (libsource (lib "Dannie Main") (part "TPAD1200"))
    )
    (comp (ref "TP13")
      (value "TPAD1200")
      (footprint "TPAD1200")
      (description "1.2mm round")
      (libsource (lib "Dannie Main") (part "TPAD1200"))
    )
    (comp (ref "TP14")
      (value "TPAD1200")
      (footprint "TPAD1200")
      (description "1.2mm round")
      (libsource (lib "Dannie Main") (part "TPAD1200"))
    )
    (comp (ref "TP15")
      (value "TPAD1200")
      (footprint "TPAD1200")
      (description "1.2mm round")
      (libsource (lib "Dannie Main") (part "TPAD1200"))
    )
    (comp (ref "TP16")
      (value "TPAD1200")
      (footprint "TPAD1200")
      (description "1.2mm round")
      (libsource (lib "Dannie Main") (part "TPAD1200"))
    )
    (comp (ref "TP17")
      (value "TPAD1200")
      (footprint "TPAD1200")
      (description "1.2mm round")
      (libsource (lib "Dannie Main") (part "TPAD1200"))
    )
    (comp (ref "TP18")
      (value "TPAD1200")
      (footprint "TPAD1200")
      (description "1.2mm round")
      (libsource (lib "Dannie Main") (part "TPAD1200"))
    )
    (comp (ref "TP19")
      (value "TPAD1200")
      (footprint "TPAD1200")
      (description "1.2mm round")
      (libsource (lib "Dannie Main") (part "TPAD1200"))
    )
    (comp (ref "TP20")
      (value "TPAD1200")
      (footprint "TPAD1200")
      (description "1.2mm round")
      (libsource (lib "Dannie Main") (part "TPAD1200"))
    )
    (comp (ref "TP21")
      (value "TPAD1200")
      (footprint "TPAD1200")
      (description "1.2mm round")
      (libsource (lib "Dannie Main") (part "TPAD1200"))
    )
    (comp (ref "TP22")
      (value "TPAD1200")
      (footprint "TPAD1200")
      (description "1.2mm round")
      (libsource (lib "Dannie Main") (part "TPAD1200"))
    )
    (comp (ref "TP23")
      (value "TPAD1200")
      (footprint "TPAD1200")
      (description "1.2mm round")
      (libsource (lib "Dannie Main") (part "TPAD1200"))
    )
    (comp (ref "TP24")
      (value "TPAD1200")
      (footprint "TPAD1200")
      (description "1.2mm round")
      (libsource (lib "Dannie Main") (part "TPAD1200"))
    )
    (comp (ref "TP25")
      (value "TPAD1200")
      (footprint "TPAD1200")
      (description "1.2mm round")
      (libsource (lib "Dannie Main") (part "TPAD1200"))
    )
    (comp (ref "TP26")
      (value "TPAD1200")
      (footprint "TPAD1200")
      (description "1.2mm round")
      (libsource (lib "Dannie Main") (part "TPAD1200"))
    )
    (comp (ref "TP27")
      (value "TPAD1200")
      (footprint "TPAD1200")
      (description "1.2mm round")
      (libsource (lib "Dannie Main") (part "TPAD1200"))
    )
    (comp (ref "TP28")
      (value "TPAD1200")
      (footprint "TPAD1200")
      (description "1.2mm round")
      (libsource (lib "Dannie Main") (part "TPAD1200"))
    )
    (comp (ref "TP29")
      (value "TPAD1200")
      (footprint "TPAD1200")
      (description "1.2mm round")
      (libsource (lib "Dannie Main") (part "TPAD1200"))
    )
    (comp (ref "U1")
      (value "VIPER115LSTR")
      (footprint "VIPER115LSTR-Footprint-1")
      (description "Converter Offline Buck, Buck-Boost, Flyback Topology 60kHz 10-SSOP")
      (libsource (lib "Dannie Main") (part "VIPER115LSTR"))
    )
    (comp (ref "U2")
      (value "AZ1117IH-3.3TRG1")
      (footprint "SOT-223-3")
      (description "Linear Voltage Regulator IC Positive Fixed 1 Output 3V3 1A SOT-223-3")
      (libsource (lib "Dannie Main") (part "AZ1117IH-5.0TRG1"))
    )
    (comp (ref "U3")
      (value "XKTF-N02-N")
      (footprint "MicroSD")
      (libsource (lib "Dannie Main") (part "XKTF-N02-N"))
    )
    (comp (ref "U4")
      (value "SP3485EN-L/TR")
      (footprint "SP3485EN-L_TR-Footprint-1")
      (description "Line Transceiver, 1 Func, 1 Driver, 1 Rcvr, BICMOS, PDSO8")
      (libsource (lib "Dannie Main") (part "SP3485EN-L/TR"))
    )
    (comp (ref "U5")
      (value "ESP32-C3-WROOM-02U-N4")
      (footprint "ESP32C3WROOM02UN4")
      (fields (field (name "MOUSER PART NUMBER") "356-ESP32C3WROM02UN4"))
      (libsource (lib "Dannie Main") (part "ESP32-C3-WROOM-02U-N4"))
    )
    (comp (ref "U6")
      (value "W5500")
      (footprint "48-LQFP (7x7)")
      (description "W5500 WIZnet Ethernet Controller 10/100 Base-T/TXPHY SPI Interface 3.3V 132mA 48-LQFP RoHS")
      (fields (field (name "MANUFACTURER") "WIZnet"))
      (libsource (lib "Dannie Main") (part "W5500"))
    )
    (comp (ref "Y1")
      (value "ABM8G-25.000MHZ-18-D2Y-T")
      (footprint "FP-ABM8G-MFG")
      (description "Crystal 25MHz ±20ppm (Tol) ±30ppm (Stability) 18pF FUND 60Ω 4-Pin SMD T/R")
      (fields (field (name "TOLERANCE") "20ppm"))
      (libsource (lib "Altium Content Vault") (part "48e526d86b7f2615d98721063c72f49"))
    )
  )
  (nets
    (net (code "1") (name "+3V3") (class "Default")
      (node (ref "C10") (pin "2") (pinfunction "2_2") (pintype "passive"))
      (node (ref "C31") (pin "2") (pinfunction "2_2") (pintype "passive"))
      (node (ref "C48") (pin "2") (pinfunction "2_2") (pintype "passive"))
      (node (ref "FB10") (pin "1") (pinfunction "1_1") (pintype "passive"))
      (node (ref "FB2") (pin "2") (pinfunction "2_2") (pintype "passive"))
      (node (ref "FB3") (pin "2") (pinfunction "2_2") (pintype "passive"))
      (node (ref "FB5") (pin "1") (pinfunction "1_1") (pintype "passive"))
      (node (ref "FB7") (pin "1") (pinfunction "1_1") (pintype "passive"))
      (node (ref "FB8") (pin "1") (pinfunction "1_1") (pintype "passive"))
      (node (ref "FB9") (pin "1") (pinfunction "1_1") (pintype "passive"))
      (node (ref "J4") (pin "10") (pinfunction "ANODE_GREEN_10") (pintype "passive"))
      (node (ref "J4") (pin "12") (pinfunction "ANODE_YELLOW_12") (pintype "passive"))
      (node (ref "R23") (pin "2") (pinfunction "2_2") (pintype "passive"))
      (node (ref "R26") (pin "2") (pinfunction "2_2") (pintype "passive"))
      (node (ref "R27") (pin "2") (pinfunction "2_2") (pintype "passive"))
      (node (ref "TP2") (pin "1") (pinfunction "TP_1") (pintype "passive"))
    )
    (net (code "2") (name "+3V3_ESP32") (class "Default")
      (node (ref "C38") (pin "2") (pinfunction "2_2") (pintype "passive"))
      (node (ref "C39") (pin "2") (pinfunction "2_2") (pintype "passive"))
      (node (ref "FB10") (pin "2") (pinfunction "2_2") (pintype "passive"))
      (node (ref "R20") (pin "1") (pinfunction "1_1") (pintype "passive"))
      (node (ref "R24") (pin "2") (pinfunction "2_2") (pintype "passive"))
      (node (ref "R28") (pin "2") (pinfunction "2_2") (pintype "passive"))
      (node (ref "R31") (pin "1") (pinfunction "1_1") (pintype "passive"))
      (node (ref "R32") (pin "1") (pinfunction "1_1") (pintype "passive"))
      (node (ref "R33") (pin "2") (pinfunction "2_2") (pintype "passive"))
      (node (ref "R45") (pin "2") (pinfunction "2_2") (pintype "passive"))
      (node (ref "U5") (pin "1") (pinfunction "3V3_1") (pintype "passive"))
    )
    (net (code "3") (name "+3V3_RGB") (class "Default")
      (node (ref "C35") (pin "2") (pinfunction "2_2") (pintype "passive"))
      (node (ref "C36") (pin "2") (pinfunction "2_2") (pintype "passive"))
      (node (ref "D11") (pin "1") (pinfunction "VDD_1") (pintype "power_in"))
      (node (ref "FB9") (pin "2") (pinfunction "2_2") (pintype "passive"))
    )
    (net (code "4") (name "+3V3_RS485") (class "Default")
      (node (ref "C20") (pin "2") (pinfunction "2_2") (pintype "passive"))
      (node (ref "C21") (pin "2") (pinfunction "2_2") (pintype "passive"))
      (node (ref "FB3") (pin "1") (pinfunction "1_1") (pintype "passive"))
      (node (ref "R21") (pin "1") (pinfunction "1_1") (pintype "passive"))
      (node (ref "U4") (pin "8") (pinfunction "VCC_8") (pintype "passive"))
    )
    (net (code "5") (name "+3V3_SDCARD") (class "Default")
      (node (ref "C27") (pin "2") (pinfunction "2_2") (pintype "passive"))
      (node (ref "C28") (pin "2") (pinfunction "2_2") (pintype "passive"))
      (node (ref "FB5") (pin "2") (pinfunction "2_2") (pintype "passive"))
      (node (ref "R11") (pin "1") (pinfunction "1_1") (pintype "passive"))
      (node (ref "R18") (pin "1") (pinfunction "1_1") (pintype "passive"))
      (node (ref "R44") (pin "1") (pinfunction "1_1") (pintype "passive"))
      (node (ref "U3") (pin "4") (pinfunction "VDD_4") (pintype "passive"))
    )
    (net (code "6") (name "+5V") (class "Default")
      (node (ref "C16") (pin "2") (pinfunction "2_2") (pintype "passive"))
      (node (ref "C17") (pin "2") (pinfunction "2_2") (pintype "passive"))
      (node (ref "C18") (pin "2") (pinfunction "2_2") (pintype "passive"))
      (node (ref "C41") (pin "2") (pinfunction "2_2") (pintype "passive"))
      (node (ref "D3") (pin "1") (pinfunction "1_1") (pintype "passive"))
      (node (ref "PI1") (pin "6") (pinfunction "Vout_+_6") (pintype "passive"))
      (node (ref "TP3") (pin "1") (pinfunction "TP_1") (pintype "passive"))
    )
    (net (code "7") (name "+5V_PR") (class "Default")
      (node (ref "C5") (pin "2") (pinfunction "2_2") (pintype "passive"))
      (node (ref "D3") (pin "2") (pinfunction "2_2") (pintype "passive"))
      (node (ref "D4") (pin "2") (pinfunction "2_2") (pintype "passive"))
      (node (ref "FB1") (pin "1") (pinfunction "1_1") (pintype "passive"))
      (node (ref "TP22") (pin "1") (pinfunction "TP_1") (pintype "passive"))
    )
    (net (code "8") (name "+5V_USB") (class "Default")
      (node (ref "C24") (pin "2") (pinfunction "2_2") (pintype "passive"))
      (node (ref "D8") (pin "5") (pinfunction "VDD_5") (pintype "passive"))
      (node (ref "FB4") (pin "1") (pinfunction "1_1") (pintype "passive"))
      (node (ref "J2") (pin "1") (pinfunction "VCC_1") (pintype "passive"))
      (node (ref "TP27") (pin "1") (pinfunction "TP_1") (pintype "passive"))
    )
    (net (code "9") (name "+5V_USB_FILT") (class "Default")
      (node (ref "C25") (pin "2") (pinfunction "2_2") (pintype "passive"))
      (node (ref "C26") (pin "2") (pinfunction "2_2") (pintype "passive"))
      (node (ref "D4") (pin "1") (pinfunction "1_1") (pintype "passive"))
      (node (ref "FB4") (pin "2") (pinfunction "2_2") (pintype "passive"))
    )
    (net (code "10") (name "/+3V3_ETH_VDDA") (class "Default")
      (node (ref "C33") (pin "2") (pinfunction "2_2") (pintype "passive"))
      (node (ref "C34") (pin "2") (pinfunction "2_2") (pintype "passive"))
      (node (ref "C51") (pin "2") (pinfunction "2_2") (pintype "passive"))
      (node (ref "C52") (pin "2") (pinfunction "2_2") (pintype "passive"))
      (node (ref "C56") (pin "2") (pinfunction "2_2") (pintype "passive"))
      (node (ref "C57") (pin "2") (pinfunction "2_2") (pintype "passive"))
      (node (ref "C58") (pin "2") (pinfunction "2_2") (pintype "passive"))
      (node (ref "FB8") (pin "2") (pinfunction "2_2") (pintype "passive"))
      (node (ref "R51") (pin "2") (pinfunction "2_2") (pintype "passive"))
      (node (ref "R52") (pin "2") (pinfunction "2_2") (pintype "passive"))
      (node (ref "R53") (pin "2") (pinfunction "2_2") (pintype "passive"))
      (node (ref "U6") (pin "11") (pinfunction "AVDD_3_11") (pintype "passive"))
      (node (ref "U6") (pin "15") (pinfunction "AVDD_4_15") (pintype "passive"))
      (node (ref "U6") (pin "17") (pinfunction "AVDD_5_17") (pintype "passive"))
      (node (ref "U6") (pin "21") (pinfunction "AVDD_6_21") (pintype "passive"))
      (node (ref "U6") (pin "4") (pinfunction "AVDD_1_4") (pintype "passive"))
      (node (ref "U6") (pin "8") (pinfunction "AVDD_2_8") (pintype "passive"))
    )
    (net (code "11") (name "/+3V3_FB") (class "Default")
      (node (ref "C8") (pin "2") (pinfunction "2_2") (pintype "passive"))
      (node (ref "C9") (pin "2") (pinfunction "2_2") (pintype "passive"))
      (node (ref "FB2") (pin "1") (pinfunction "1_1") (pintype "passive"))
      (node (ref "U2") (pin "2") (pinfunction "Vout_2") (pintype "passive"))
    )
    (net (code "12") (name "/AC_L") (class "Default")
      (node (ref "BR1") (pin "3") (pinfunction "~_3") (pintype "passive"))
      (node (ref "C42") (pin "1") (pinfunction "1_1") (pintype "passive"))
      (node (ref "R2") (pin "2") (pinfunction "2_2") (pintype "passive"))
      (node (ref "RT1") (pin "2") (pinfunction "2_2") (pintype "passive"))
    )
    (net (code "13") (name "/DC_F") (class "Default")
      (node (ref "C3") (pin "1") (pinfunction "P_1") (pintype "passive"))
      (node (ref "L1") (pin "2") (pinfunction "2_2") (pintype "passive"))
      (node (ref "TP18") (pin "1") (pinfunction "TP_1") (pintype "passive"))
      (node (ref "U1") (pin "10") (pinfunction "D_10") (pintype "passive"))
      (node (ref "U1") (pin "6") (pinfunction "D_6") (pintype "passive"))
      (node (ref "U1") (pin "7") (pinfunction "D_7") (pintype "passive"))
      (node (ref "U1") (pin "8") (pinfunction "D_8") (pintype "passive"))
      (node (ref "U1") (pin "9") (pinfunction "D_9") (pintype "passive"))
    )
    (net (code "14") (name "/DC_L") (class "Default")
      (node (ref "BR1") (pin "1") (pinfunction "+_1") (pintype "passive"))
      (node (ref "C2") (pin "1") (pinfunction "P_1") (pintype "passive"))
      (node (ref "L1") (pin "1") (pinfunction "1_1") (pintype "passive"))
      (node (ref "R4") (pin "2") (pinfunction "2_2") (pintype "passive"))
      (node (ref "R5") (pin "2") (pinfunction "2_2") (pintype "passive"))
      (node (ref "TP17") (pin "1") (pinfunction "TP_1") (pintype "passive"))
    )
    (net (code "15") (name "/ESP32_BOOT") (class "Default")
      (node (ref "C4") (pin "2") (pinfunction "2_2") (pintype "passive"))
      (node (ref "R20") (pin "2") (pinfunction "2_2") (pintype "passive"))
      (node (ref "S3") (pin "2") (pinfunction "2_2") (pintype "passive"))
      (node (ref "TP19") (pin "1") (pinfunction "TP_1") (pintype "passive"))
      (node (ref "U5") (pin "8") (pinfunction "IO9_8") (pintype "passive"))
    )
    (net (code "16") (name "/ESP32_CLK") (class "Default")
      (node (ref "R29") (pin "2") (pinfunction "2_2") (pintype "passive"))
      (node (ref "TP8") (pin "1") (pinfunction "TP_1") (pintype "passive"))
      (node (ref "U3") (pin "5") (pinfunction "CLK/SPI-CLK_5") (pintype "passive"))
      (node (ref "U6") (pin "33") (pinfunction "SCLK_33") (pintype "passive"))
    )
    (net (code "17") (name "/ESP32_CLK_+3V3") (class "Default")
      (node (ref "R29") (pin "1") (pinfunction "1_1") (pintype "passive"))
      (node (ref "U5") (pin "5") (pinfunction "IO6_5") (pintype "passive"))
    )
    (net (code "18") (name "/ESP32_EN_+3V3") (class "Default")
      (node (ref "C40") (pin "2") (pinfunction "2_2") (pintype "passive"))
      (node (ref "R33") (pin "1") (pinfunction "1_1") (pintype "passive"))
      (node (ref "S2") (pin "2") (pinfunction "2_2") (pintype "passive"))
      (node (ref "TP20") (pin "1") (pinfunction "TP_1") (pintype "passive"))
      (node (ref "U5") (pin "2") (pinfunction "EN_2") (pintype "passive"))
    )
    (net (code "19") (name "/ESP32_ETH_CS") (class "Default")
      (node (ref "R36") (pin "2") (pinfunction "2_2") (pintype "passive"))
      (node (ref "TP11") (pin "1") (pinfunction "TP_1") (pintype "passive"))
      (node (ref "U6") (pin "32") (pinfunction "SCSN_32") (pintype "passive"))
    )
    (net (code "20") (name "/ESP32_ETH_CS_+3V3") (class "Default")
      (node (ref "R36") (pin "1") (pinfunction "1_1") (pintype "passive"))
      (node (ref "R45") (pin "1") (pinfunction "1_1") (pintype "passive"))
      (node (ref "U5") (pin "17") (pinfunction "IO1_17") (pintype "passive"))
    )
    (net (code "21") (name "/ESP32_ETH_INT") (class "Default")
      (node (ref "R38") (pin "2") (pinfunction "2_2") (pintype "passive"))
      (node (ref "U6") (pin "36") (pinfunction "INTN_36") (pintype "passive"))
    )
    (net (code "22") (name "/ESP32_ETH_INT_+3V3") (class "Default")
      (node (ref "R28") (pin "1") (pinfunction "1_1") (pintype "passive"))
      (node (ref "R38") (pin "1") (pinfunction "1_1") (pintype "passive"))
      (node (ref "U5") (pin "18") (pinfunction "IO0_18") (pintype "passive"))
    )
    (net (code "23") (name "/ESP32_ETH_RST") (class "Default")
      (node (ref "R37") (pin "2") (pinfunction "2_2") (pintype "passive"))
      (node (ref "U6") (pin "37") (pinfunction "RSTN_37") (pintype "passive"))
    )
    (net (code "24") (name "/ESP32_ETH_RST_+3V3") (class "Default")
      (node (ref "R32") (pin "2") (pinfunction "2_2") (pintype "passive"))
      (node (ref "R37") (pin "1") (pinfunction "1_1") (pintype "passive"))
      (node (ref "U5") (pin "7") (pinfunction "IO8_7") (pintype "passive"))
    )
    (net (code "25") (name "/ESP32_MISO") (class "Default")
      (node (ref "R34") (pin "2") (pinfunction "2_2") (pintype "passive"))
      (node (ref "TP10") (pin "1") (pinfunction "TP_1") (pintype "passive"))
      (node (ref "U3") (pin "7") (pinfunction "DATO/SPI-MISO_7") (pintype "passive"))
      (node (ref "U6") (pin "34") (pinfunction "MISO_34") (pintype "passive"))
    )
    (net (code "26") (name "/ESP32_MISO_+3V3") (class "Default")
      (node (ref "R31") (pin "2") (pinfunction "2_2") (pintype "passive"))
      (node (ref "R34") (pin "1") (pinfunction "1_1") (pintype "passive"))
      (node (ref "U5") (pin "16") (pinfunction "IO2_16") (pintype "passive"))
    )
    (net (code "27") (name "/ESP32_MOSI") (class "Default")
      (node (ref "R30") (pin "2") (pinfunction "2_2") (pintype "passive"))
      (node (ref "TP9") (pin "1") (pinfunction "TP_1") (pintype "passive"))
      (node (ref "U3") (pin "3") (pinfunction "CMD/SPI-MOSI_3") (pintype "passive"))
      (node (ref "U6") (pin "35") (pinfunction "MOSI_35") (pintype "passive"))
    )
    (net (code "28") (name "/ESP32_MOSI_+3V3") (class "Default")
      (node (ref "R30") (pin "1") (pinfunction "1_1") (pintype "passive"))
      (node (ref "U5") (pin "6") (pinfunction "IO7_6") (pintype "passive"))
    )
    (net (code "29") (name "/ESP32_RGB_+3V3") (class "Default")
      (node (ref "R25") (pin "2") (pinfunction "2_2") (pintype "passive"))
      (node (ref "U5") (pin "4") (pinfunction "IO5_4") (pintype "passive"))
    )
    (net (code "30") (name "/ESP32_RS485_DIR") (class "Default")
      (node (ref "R14") (pin "2") (pinfunction "2_2") (pintype "passive"))
      (node (ref "R16") (pin "1") (pinfunction "1_1") (pintype "passive"))
      (node (ref "U4") (pin "2") (pinfunction "~{RE}_2") (pintype "passive"))
      (node (ref "U4") (pin "3") (pinfunction "DE_3") (pintype "passive"))
    )
    (net (code "31") (name "/ESP32_RS485_DIR_+3V3") (class "Default")
      (node (ref "R14") (pin "1") (pinfunction "1_1") (pintype "passive"))
      (node (ref "U5") (pin "3") (pinfunction "IO4_3") (pintype "passive"))
    )
    (net (code "32") (name "/ESP32_RS485_RX") (class "Default")
      (node (ref "R13") (pin "2") (pinfunction "2_2") (pintype "passive"))
      (node (ref "TP14") (pin "1") (pinfunction "TP_1") (pintype "passive"))
      (node (ref "U4") (pin "1") (pinfunction "RO_1") (pintype "passive"))
    )
    (net (code "33") (name "/ESP32_RS485_RX_+3V3") (class "Default")
      (node (ref "R13") (pin "1") (pinfunction "1_1") (pintype "passive"))
      (node (ref "U5") (pin "11") (pinfunction "RXD_11") (pintype "passive"))
    )
    (net (code "34") (name "/ESP32_RS485_TX") (class "Default")
      (node (ref "R15") (pin "2") (pinfunction "2_2") (pintype "passive"))
      (node (ref "TP13") (pin "1") (pinfunction "TP_1") (pintype "passive"))
      (node (ref "U4") (pin "4") (pinfunction "DI_4") (pintype "passive"))
    )
    (net (code "35") (name "/ESP32_RS485_TX_+3V3") (class "Default")
      (node (ref "R15") (pin "1") (pinfunction "1_1") (pintype "passive"))
      (node (ref "U5") (pin "12") (pinfunction "TXD_12") (pintype "passive"))
    )
    (net (code "36") (name "/ESP32_SDCARD_CS") (class "Default")
      (node (ref "R11") (pin "2") (pinfunction "2_2") (pintype "passive"))
      (node (ref "R35") (pin "2") (pinfunction "2_2") (pintype "passive"))
      (node (ref "TP12") (pin "1") (pinfunction "TP_1") (pintype "passive"))
      (node (ref "U3") (pin "2") (pinfunction "CD/DAT3/SPI-CS_2") (pintype "passive"))
    )
    (net (code "37") (name "/ESP32_SDCARD_CS_+3V3") (class "Default")
      (node (ref "R35") (pin "1") (pinfunction "1_1") (pintype "passive"))
      (node (ref "U5") (pin "10") (pinfunction "IO10_10") (pintype "passive"))
    )
    (net (code "38") (name "/ESP32_USB_D_N") (class "Default")
      (node (ref "R39") (pin "1") (pinfunction "1_1") (pintype "passive"))
      (node (ref "U5") (pin "13") (pinfunction "IO18_13") (pintype "passive"))
    )
    (net (code "39") (name "/ESP32_USB_D_P") (class "Default")
      (node (ref "R40") (pin "1") (pinfunction "1_1") (pintype "passive"))
      (node (ref "U5") (pin "14") (pinfunction "IO19_14") (pintype "passive"))
    )
    (net (code "40") (name "/ESP32_USER_BTN_+3V3") (class "Default")
      (node (ref "C37") (pin "2") (pinfunction "2_2") (pintype "passive"))
      (node (ref "R24") (pin "1") (pinfunction "1_1") (pintype "passive"))
      (node (ref "S1") (pin "2") (pinfunction "2_2") (pintype "passive"))
      (node (ref "TP29") (pin "1") (pinfunction "TP_1") (pintype "passive"))
      (node (ref "U5") (pin "15") (pinfunction "IO3_15") (pintype "passive"))
    )
    (net (code "41") (name "/ETH_1V2O") (class "Default")
      (node (ref "C55") (pin "2") (pinfunction "2_2") (pintype "passive"))
      (node (ref "U6") (pin "22") (pinfunction "1V2O_22") (pintype "passive"))
    )
    (net (code "42") (name "/ETH_EXRES") (class "Default")
      (node (ref "R63") (pin "2") (pinfunction "2_2") (pintype "passive"))
      (node (ref "U6") (pin "10") (pinfunction "EXRES1_10") (pintype "passive"))
    )
    (net (code "43") (name "/ETH_LED_ACT") (class "Default")
      (node (ref "R61") (pin "2") (pinfunction "2_2") (pintype "passive"))
      (node (ref "U6") (pin "27") (pinfunction "ACTLED_27") (pintype "passive"))
    )
    (net (code "44") (name "/ETH_LED_LINK") (class "Default")
      (node (ref "R62") (pin "2") (pinfunction "2_2") (pintype "passive"))
      (node (ref "U6") (pin "25") (pinfunction "LINKLED_25") (pintype "passive"))
    )
    (net (code "45") (name "/ETH_PMODE0") (class "Default")
      (node (ref "R27") (pin "1") (pinfunction "1_1") (pintype "passive"))
      (node (ref "R43") (pin "2") (pinfunction "2_2") (pintype "passive"))
      (node (ref "U6") (pin "45") (pinfunction "PMODE0_45") (pintype "passive"))
    )
    (net (code "46") (name "/ETH_PMODE1") (class "Default")
      (node (ref "R26") (pin "1") (pinfunction "1_1") (pintype "passive"))
      (node (ref "R42") (pin "2") (pinfunction "2_2") (pintype "passive"))
      (node (ref "U6") (pin "44") (pinfunction "PMODE1_44") (pintype "passive"))
    )
    (net (code "47") (name "/ETH_PMODE2") (class "Default")
      (node (ref "R23") (pin "1") (pinfunction "1_1") (pintype "passive"))
      (node (ref "R41") (pin "2") (pinfunction "2_2") (pintype "passive"))
      (node (ref "U6") (pin "43") (pinfunction "PMODE2_43") (pintype "passive"))
    )
    (net (code "48") (name "/ETH_RSVD2") (class "Default")
      (node (ref "R46") (pin "1") (pinfunction "1_1") (pintype "passive"))
      (node (ref "U6") (pin "38") (pinfunction "RSVD_2_38") (pintype "passive"))
    )
    (net (code "49") (name "/ETH_RSVD3") (class "Default")
      (node (ref "R47") (pin "1") (pinfunction "1_1") (pintype "passive"))
      (node (ref "U6") (pin "39") (pinfunction "RSVD_3_39") (pintype "passive"))
    )
    (net (code "50") (name "/ETH_RSVD4") (class "Default")
      (node (ref "R48") (pin "1") (pinfunction "1_1") (pintype "passive"))
      (node (ref "U6") (pin "40") (pinfunction "RSVD_4_40") (pintype "passive"))
    )
    (net (code "51") (name "/ETH_RSVD5") (class "Default")
      (node (ref "R49") (pin "1") (pinfunction "1_1") (pintype "passive"))
      (node (ref "U6") (pin "41") (pinfunction "RSVD_5_41") (pintype "passive"))
    )
    (net (code "52") (name "/ETH_RSVD6") (class "Default")
      (node (ref "R50") (pin "1") (pinfunction "1_1") (pintype "passive"))
      (node (ref "U6") (pin "42") (pinfunction "RSVD_6_42") (pintype "passive"))
    )
    (net (code "53") (name "/ETH_RXN") (class "Default")
      (node (ref "R56") (pin "1") (pinfunction "1_1") (pintype "passive"))
      (node (ref "U6") (pin "5") (pinfunction "RXN_5") (pintype "passive"))
    )
    (net (code "54") (name "/ETH_RXN_2") (class "Default")
      (node (ref "C45") (pin "1") (pinfunction "1_1") (pintype "passive"))
      (node (ref "R56") (pin "2") (pinfunction "2_2") (pintype "passive"))
      (node (ref "R60") (pin "2") (pinfunction "2_2") (pintype "passive"))
    )
    (net (code "55") (name "/ETH_RXP") (class "Default")
      (node (ref "R58") (pin "1") (pinfunction "1_1") (pintype "passive"))
      (node (ref "U6") (pin "6") (pinfunction "RXP_6") (pintype "passive"))
    )
    (net (code "56") (name "/ETH_RXP_2") (class "Default")
      (node (ref "C46") (pin "1") (pinfunction "1_1") (pintype "passive"))
      (node (ref "R58") (pin "2") (pinfunction "2_2") (pintype "passive"))
      (node (ref "R59") (pin "2") (pinfunction "2_2") (pintype "passive"))
    )
    (net (code "57") (name "/ETH_TOCAP") (class "Default")
      (node (ref "C54") (pin "2") (pinfunction "2_2") (pintype "passive"))
      (node (ref "U6") (pin "20") (pinfunction "TOCAP_20") (pintype "passive"))
    )
    (net (code "58") (name "/ETH_TXN") (class "Default")
      (node (ref "R54") (pin "1") (pinfunction "1_1") (pintype "passive"))
      (node (ref "U6") (pin "1") (pinfunction "TXN_1") (pintype "passive"))
    )
    (net (code "59") (name "/ETH_TXN_2") (class "Default")
      (node (ref "J4") (pin "3") (pinfunction "3_3") (pintype "passive"))
      (node (ref "R51") (pin "1") (pinfunction "1_1") (pintype "passive"))
      (node (ref "R54") (pin "2") (pinfunction "2_2") (pintype "passive"))
    )
    (net (code "60") (name "/ETH_TXP") (class "Default")
      (node (ref "R55") (pin "1") (pinfunction "1_1") (pintype "passive"))
      (node (ref "U6") (pin "2") (pinfunction "TXP_2") (pintype "passive"))
    )
    (net (code "61") (name "/ETH_TXP_2") (class "Default")
      (node (ref "J4") (pin "1") (pinfunction "1_1") (pintype "passive"))
      (node (ref "R52") (pin "1") (pinfunction "1_1") (pintype "passive"))
      (node (ref "R55") (pin "2") (pinfunction "2_2") (pintype "passive"))
    )
    (net (code "62") (name "/ETH_VDD") (class "Default")
      (node (ref "C49") (pin "2") (pinfunction "2_2") (pintype "passive"))
      (node (ref "C50") (pin "2") (pinfunction "2_2") (pintype "passive"))
      (node (ref "FB7") (pin "2") (pinfunction "2_2") (pintype "passive"))
      (node (ref "U6") (pin "28") (pinfunction "VDD_28") (pintype "passive"))
    )
    (net (code "63") (name "/ETH_XI") (class "Default")
      (node (ref "C47") (pin "2") (pinfunction "2_2") (pintype "passive"))
      (node (ref "R57") (pin "1") (pinfunction "1_1") (pintype "passive"))
      (node (ref "U6") (pin "30") (pinfunction "XI/CLKIN_30") (pintype "passive"))
      (node (ref "Y1") (pin "3") (pinfunction "3_3") (pintype "passive"))
    )
    (net (code "64") (name "/ETH_XO") (class "Default")
      (node (ref "C43") (pin "2") (pinfunction "2_2") (pintype "passive"))
      (node (ref "R57") (pin "2") (pinfunction "2_2") (pintype "passive"))
      (node (ref "U6") (pin "31") (pinfunction "XO_31") (pintype "passive"))
      (node (ref "Y1") (pin "1") (pinfunction "1_1") (pintype "passive"))
    )
    (net (code "65") (name "/LED_ACT") (class "Default")
      (node (ref "J4") (pin "9") (pinfunction "CATHODE_GREEN_9") (pintype "passive"))
      (node (ref "R61") (pin "1") (pinfunction "1_1") (pintype "passive"))
    )
    (net (code "66") (name "/LED_LINK") (class "Default")
      (node (ref "J4") (pin "11") (pinfunction "CATHODE_YELLOW_11") (pintype "passive"))
      (node (ref "R62") (pin "1") (pinfunction "1_1") (pintype "passive"))
    )
    (net (code "67") (name "/PR_USB_D_N") (class "Default")
      (node (ref "D8") (pin "3") (pinfunction "I/O_2_3") (pintype "passive"))
      (node (ref "R39") (pin "2") (pinfunction "2_2") (pintype "passive"))
    )
    (net (code "68") (name "/PR_USB_D_P") (class "Default")
      (node (ref "D8") (pin "1") (pinfunction "I/O_1_1") (pintype "passive"))
      (node (ref "R40") (pin "2") (pinfunction "2_2") (pintype "passive"))
    )
    (net (code "69") (name "/RS485_A") (class "Default")
      (node (ref "D9") (pin "2") (pinfunction "C2_2") (pintype "passive"))
      (node (ref "J3") (pin "1") (pinfunction "1_1") (pintype "passive"))
      (node (ref "R17") (pin "1") (pinfunction "1_1") (pintype "passive"))
      (node (ref "R19") (pin "2") (pinfunction "2_2") (pintype "passive"))
      (node (ref "TP7") (pin "1") (pinfunction "TP_1") (pintype "passive"))
    )
    (net (code "70") (name "/RS485_A1") (class "Default")
      (node (ref "C23") (pin "1") (pinfunction "1_1") (pintype "passive"))
      (node (ref "C29") (pin "2") (pinfunction "2_2") (pintype "passive"))
      (node (ref "R19") (pin "1") (pinfunction "1_1") (pintype "passive"))
      (node (ref "R21") (pin "2") (pinfunction "2_2") (pintype "passive"))
      (node (ref "U4") (pin "6") (pinfunction "A_6") (pintype "passive"))
    )
    (net (code "71") (name "/RS485_B") (class "Default")
      (node (ref "D9") (pin "1") (pinfunction "C1_1") (pintype "passive"))
      (node (ref "J3") (pin "2") (pinfunction "2_2") (pintype "passive"))
      (node (ref "R10") (pin "2") (pinfunction "2_2") (pintype "passive"))
      (node (ref "R12") (pin "2") (pinfunction "2_2") (pintype "passive"))
      (node (ref "TP6") (pin "1") (pinfunction "TP_1") (pintype "passive"))
    )
    (net (code "72") (name "/RS485_B1") (class "Default")
      (node (ref "C19") (pin "1") (pinfunction "1_1") (pintype "passive"))
      (node (ref "C23") (pin "2") (pinfunction "2_2") (pintype "passive"))
      (node (ref "R10") (pin "1") (pinfunction "1_1") (pintype "passive"))
      (node (ref "R9") (pin "1") (pinfunction "1_1") (pintype "passive"))
      (node (ref "U4") (pin "7") (pinfunction "B_7") (pintype "passive"))
    )
    (net (code "73") (name "/SDCARD_DAT1") (class "Default")
      (node (ref "R18") (pin "2") (pinfunction "2_2") (pintype "passive"))
      (node (ref "U3") (pin "8") (pinfunction "DAT1_8") (pintype "passive"))
    )
    (net (code "74") (name "/USB_D_N") (class "Default")
      (node (ref "D8") (pin "4") (pinfunction "I/O_2_4") (pintype "passive"))
      (node (ref "J2") (pin "2") (pinfunction "D-_2") (pintype "passive"))
      (node (ref "TP4") (pin "1") (pinfunction "TP_1") (pintype "passive"))
    )
    (net (code "75") (name "/USB_D_P") (class "Default")
      (node (ref "D8") (pin "6") (pinfunction "I/O_1_6") (pintype "passive"))
      (node (ref "J2") (pin "3") (pinfunction "D+_3") (pintype "passive"))
      (node (ref "TP5") (pin "1") (pinfunction "TP_1") (pintype "passive"))
    )
    (net (code "76") (name "/VIN_+5V") (class "Default")
      (node (ref "C6") (pin "2") (pinfunction "2_2") (pintype "passive"))
      (node (ref "C7") (pin "2") (pinfunction "2_2") (pintype "passive"))
      (node (ref "FB1") (pin "2") (pinfunction "2_2") (pintype "passive"))
      (node (ref "U2") (pin "3") (pinfunction "Vin_3") (pintype "passive"))
    )
    (net (code "77") (name "/VIPER_FB") (class "Default")
      (node (ref "R1") (pin "1") (pinfunction "1_1") (pintype "passive"))
      (node (ref "R6") (pin "2") (pinfunction "2_2") (pintype "passive"))
      (node (ref "U1") (pin "4") (pinfunction "FB_4") (pintype "passive"))
    )
    (net (code "78") (name "/VIPER_RT1") (class "Default")
      (node (ref "C13") (pin "2") (pinfunction "2_2") (pintype "passive"))
      (node (ref "D5") (pin "1") (pinfunction "A_1") (pintype "passive"))
      (node (ref "D6") (pin "2") (pinfunction "2_2") (pintype "passive"))
      (node (ref "R7") (pin "1") (pinfunction "1_1") (pintype "passive"))
    )
    (net (code "79") (name "/VIPER_S") (class "Default")
      (node (ref "C1") (pin "2") (pinfunction "2_2") (pintype "passive"))
      (node (ref "C11") (pin "1") (pinfunction "1_1") (pintype "passive"))
      (node (ref "C12") (pin "1") (pinfunction "1_1") (pintype "passive"))
      (node (ref "C13") (pin "1") (pinfunction "1_1") (pintype "passive"))
      (node (ref "D7") (pin "2") (pinfunction "2_2") (pintype "passive"))
      (node (ref "L2") (pin "2") (pinfunction "2_2") (pintype "passive"))
      (node (ref "R1") (pin "2") (pinfunction "2_2") (pintype "passive"))
      (node (ref "U1") (pin "1") (pinfunction "GND_1") (pintype "passive"))
      (node (ref "U1") (pin "3") (pinfunction "DIS_3") (pintype "passive"))
    )
    (net (code "80") (name "/VIPER_VCC") (class "Default")
      (node (ref "C11") (pin "2") (pinfunction "2_2") (pintype "passive"))
      (node (ref "C12") (pin "2") (pinfunction "2_2") (pintype "passive"))
      (node (ref "D5") (pin "2") (pinfunction "K_2") (pintype "passive"))
      (node (ref "U1") (pin "2") (pinfunction "VCC_2") (pintype "passive"))
    )
    (net (code "81") (name "GND") (class "Default")
      (node (ref "C10") (pin "1") (pinfunction "1_1") (pintype "passive"))
      (node (ref "C16") (pin "1") (pinfunction "1_1") (pintype "passive"))
      (node (ref "C17") (pin "1") (pinfunction "1_1") (pintype "passive"))
      (node (ref "C18") (pin "1") (pinfunction "1_1") (pintype "passive"))
      (node (ref "C19") (pin "2") (pinfunction "2_2") (pintype "passive"))
      (node (ref "C20") (pin "1") (pinfunction "1_1") (pintype "passive"))
      (node (ref "C21") (pin "1") (pinfunction "1_1") (pintype "passive"))
      (node (ref "C22") (pin "1") (pinfunction "1_1") (pintype "passive"))
      (node (ref "C24") (pin "1") (pinfunction "1_1") (pintype "passive"))
      (node (ref "C25") (pin "1") (pinfunction "1_1") (pintype "passive"))
      (node (ref "C26") (pin "1") (pinfunction "1_1") (pintype "passive"))
      (node (ref "C27") (pin "1") (pinfunction "1_1") (pintype "passive"))
      (node (ref "C28") (pin "1") (pinfunction "1_1") (pintype "passive"))
      (node (ref "C29") (pin "1") (pinfunction "1_1") (pintype "passive"))
      (node (ref "C30") (pin "1") (pinfunction "1_1") (pintype "passive"))
      (node (ref "C31") (pin "1") (pinfunction "1_1") (pintype "passive"))
      (node (ref "C32") (pin "1") (pinfunction "1_1") (pintype "passive"))
      (node (ref "C33") (pin "1") (pinfunction "1_1") (pintype "passive"))
      (node (ref "C34") (pin "1") (pinfunction "1_1") (pintype "passive"))
      (node (ref "C35") (pin "1") (pinfunction "1_1") (pintype "passive"))
      (node (ref "C36") (pin "1") (pinfunction "1_1") (pintype "passive"))
      (node (ref "C37") (pin "1") (pinfunction "1_1") (pintype "passive"))
      (node (ref "C38") (pin "1") (pinfunction "1_1") (pintype "passive"))
      (node (ref "C39") (pin "1") (pinfunction "1_1") (pintype "passive"))
      (node (ref "C4") (pin "1") (pinfunction "1_1") (pintype "passive"))
      (node (ref "C40") (pin "1") (pinfunction "1_1") (pintype "passive"))
      (node (ref "C41") (pin "1") (pinfunction "1_1") (pintype "passive"))
      (node (ref "C43") (pin "1") (pinfunction "1_1") (pintype "passive"))
      (node (ref "C44") (pin "1") (pinfunction "1_1") (pintype "passive"))
      (node (ref "C47") (pin "1") (pinfunction "1_1") (pintype "passive"))
      (node (ref "C48") (pin "1") (pinfunction "1_1") (pintype "passive"))
      (node (ref "C49") (pin "1") (pinfunction "1_1") (pintype "passive"))
      (node (ref "C5") (pin "1") (pinfunction "1_1") (pintype "passive"))
      (node (ref "C50") (pin "1") (pinfunction "1_1") (pintype "passive"))
      (node (ref "C51") (pin "1") (pinfunction "1_1") (pintype "passive"))
      (node (ref "C52") (pin "1") (pinfunction "1_1") (pintype "passive"))
      (node (ref "C53") (pin "1") (pinfunction "1_1") (pintype "passive"))
      (node (ref "C54") (pin "1") (pinfunction "1_1") (pintype "passive"))
      (node (ref "C55") (pin "1") (pinfunction "1_1") (pintype "passive"))
      (node (ref "C56") (pin "1") (pinfunction "1_1") (pintype "passive"))
      (node (ref "C57") (pin "1") (pinfunction "1_1") (pintype "passive"))
      (node (ref "C58") (pin "1") (pinfunction "1_1") (pintype "passive"))
      (node (ref "C6") (pin "1") (pinfunction "1_1") (pintype "passive"))
      (node (ref "C7") (pin "1") (pinfunction "1_1") (pintype "passive"))
      (node (ref "C8") (pin "1") (pinfunction "1_1") (pintype "passive"))
      (node (ref "C9") (pin "1") (pinfunction "1_1") (pintype "passive"))
      (node (ref "D11") (pin "3") (pinfunction "VSS_3") (pintype "power_in"))
      (node (ref "D8") (pin "2") (pinfunction "GND_2") (pintype "passive"))
      (node (ref "D9") (pin "3") (pinfunction "CC_3") (pintype "passive"))
      (node (ref "FB6") (pin "2") (pinfunction "2_2") (pintype "passive"))
      (node (ref "PI1") (pin "4") (pinfunction "Vout_-_4") (pintype "passive"))
      (node (ref "R16") (pin "2") (pinfunction "2_2") (pintype "passive"))
      (node (ref "R22") (pin "1") (pinfunction "1_1") (pintype "passive"))
      (node (ref "R41") (pin "1") (pinfunction "1_1") (pintype "passive"))
      (node (ref "R42") (pin "1") (pinfunction "1_1") (pintype "passive"))
      (node (ref "R43") (pin "1") (pinfunction "1_1") (pintype "passive"))
      (node (ref "R46") (pin "2") (pinfunction "2_2") (pintype "passive"))
      (node (ref "R47") (pin "2") (pinfunction "2_2") (pintype "passive"))
      (node (ref "R48") (pin "2") (pinfunction "2_2") (pintype "passive"))
      (node (ref "R49") (pin "2") (pinfunction "2_2") (pintype "passive"))
      (node (ref "R50") (pin "2") (pinfunction "2_2") (pintype "passive"))
      (node (ref "R63") (pin "1") (pinfunction "1_1") (pintype "passive"))
      (node (ref "R9") (pin "2") (pinfunction "2_2") (pintype "passive"))
      (node (ref "S1") (pin "1") (pinfunction "1_1") (pintype "passive"))
      (node (ref "S2") (pin "1") (pinfunction "1_1") (pintype "passive"))
      (node (ref "S3") (pin "1") (pinfunction "1_1") (pintype "passive"))
      (node (ref "TP15") (pin "1") (pinfunction "TP_1") (pintype "passive"))
      (node (ref "TP16") (pin "1") (pinfunction "TP_1") (pintype "passive"))
      (node (ref "U2") (pin "1") (pinfunction "Gnd_1") (pintype "passive"))
      (node (ref "U3") (pin "6") (pinfunction "VSS_6") (pintype "passive"))
      (node (ref "U3") (pin "G1") (pinfunction "G1_G1") (pintype "passive"))
      (node (ref "U3") (pin "G2") (pinfunction "G2_G2") (pintype "passive"))
      (node (ref "U3") (pin "G3") (pinfunction "G3_G3") (pintype "passive"))
      (node (ref "U3") (pin "G4") (pinfunction "G4_G4") (pintype "passive"))
      (node (ref "U4") (pin "5") (pinfunction "GND_5") (pintype "passive"))
      (node (ref "U5") (pin "19") (pinfunction "PAD_19") (pintype "passive"))
      (node (ref "U5") (pin "9") (pinfunction "GND_9") (pintype "passive"))
      (node (ref "U6") (pin "14") (pinfunction "AGND_3_14") (pintype "passive"))
      (node (ref "U6") (pin "16") (pinfunction "AGND_4_16") (pintype "passive"))
      (node (ref "U6") (pin "19") (pinfunction "AGND_5_19") (pintype "passive"))
      (node (ref "U6") (pin "29") (pinfunction "GND_29") (pintype "passive"))
      (node (ref "U6") (pin "3") (pinfunction "AGND_1_3") (pintype "passive"))
      (node (ref "U6") (pin "48") (pinfunction "AGND_6_48") (pintype "passive"))
      (node (ref "U6") (pin "9") (pinfunction "AGND_2_9") (pintype "passive"))
      (node (ref "Y1") (pin "2") (pinfunction "GND_2") (pintype "power_in"))
      (node (ref "Y1") (pin "4") (pinfunction "GND_4") (pintype "power_in"))
    )
    (net (code "82") (name "GND_CH") (class "Default")
      (node (ref "C32") (pin "2") (pinfunction "2_2") (pintype "passive"))
      (node (ref "J4") (pin "13") (pinfunction "MNT_1_13") (pintype "passive"))
      (node (ref "J4") (pin "14") (pinfunction "MNT_2_14") (pintype "passive"))
      (node (ref "J4") (pin "8") (pinfunction "8_8") (pintype "passive"))
    )
    (net (code "83") (name "GND_HV") (class "Default")
      (node (ref "BR1") (pin "2") (pinfunction "-_2") (pintype "passive"))
      (node (ref "C14") (pin "2") (pinfunction "2_2") (pintype "passive"))
      (node (ref "C15") (pin "1") (pinfunction "1_1") (pintype "passive"))
      (node (ref "C2") (pin "2") (pinfunction "N_2") (pintype "passive"))
      (node (ref "C3") (pin "2") (pinfunction "N_2") (pintype "passive"))
      (node (ref "D7") (pin "1") (pinfunction "1_1") (pintype "passive"))
      (node (ref "PI1") (pin "2") (pinfunction "Vin_-_2") (pintype "passive"))
      (node (ref "R4") (pin "1") (pinfunction "1_1") (pintype "passive"))
      (node (ref "R5") (pin "1") (pinfunction "1_1") (pintype "passive"))
      (node (ref "R8") (pin "1") (pinfunction "1_1") (pintype "passive"))
      (node (ref "TP24") (pin "1") (pinfunction "TP_1") (pintype "passive"))
      (node (ref "TP25") (pin "1") (pinfunction "TP_1") (pintype "passive"))
    )
    (net (code "84") (name "NI_5V") (class "Default")
      (node (ref "C14") (pin "1") (pinfunction "1_1") (pintype "passive"))
      (node (ref "C15") (pin "2") (pinfunction "2_2") (pintype "passive"))
      (node (ref "D6") (pin "1") (pinfunction "1_1") (pintype "passive"))
      (node (ref "L2") (pin "1") (pinfunction "1_1") (pintype "passive"))
      (node (ref "PI1") (pin "1") (pinfunction "Vin_+_1") (pintype "passive"))
      (node (ref "R8") (pin "2") (pinfunction "2_2") (pintype "passive"))
      (node (ref "TP21") (pin "1") (pinfunction "TP_1") (pintype "passive"))
    )
    (net (code "85") (name "Net-(C1-Pad1)") (class "Default")
      (node (ref "C1") (pin "1") (pinfunction "1_1") (pintype "passive"))
      (node (ref "R3") (pin "2") (pinfunction "2_2") (pintype "passive"))
    )
    (net (code "86") (name "Net-(C22-Pad2)") (class "Default")
      (node (ref "C22") (pin "2") (pinfunction "2_2") (pintype "passive"))
      (node (ref "R12") (pin "1") (pinfunction "1_1") (pintype "passive"))
      (node (ref "R17") (pin "2") (pinfunction "2_2") (pintype "passive"))
    )
    (net (code "87") (name "Net-(C44-Pad2)") (class "Default")
      (node (ref "C44") (pin "2") (pinfunction "2_2") (pintype "passive"))
      (node (ref "J4") (pin "2") (pinfunction "2_2") (pintype "passive"))
      (node (ref "R53") (pin "1") (pinfunction "1_1") (pintype "passive"))
    )
    (net (code "88") (name "Net-(C45-Pad2)") (class "Default")
      (node (ref "C45") (pin "2") (pinfunction "2_2") (pintype "passive"))
      (node (ref "J4") (pin "6") (pinfunction "6_6") (pintype "passive"))
    )
    (net (code "89") (name "Net-(C46-Pad2)") (class "Default")
      (node (ref "C46") (pin "2") (pinfunction "2_2") (pintype "passive"))
      (node (ref "J4") (pin "4") (pinfunction "4_4") (pintype "passive"))
    )
    (net (code "90") (name "Net-(C53-Pad2)") (class "Default")
      (node (ref "C53") (pin "2") (pinfunction "2_2") (pintype "passive"))
      (node (ref "J4") (pin "5") (pinfunction "5_5") (pintype "passive"))
      (node (ref "R59") (pin "1") (pinfunction "1_1") (pintype "passive"))
      (node (ref "R60") (pin "1") (pinfunction "1_1") (pintype "passive"))
    )
    (net (code "91") (name "Net-(D11-DIN)") (class "Default")
      (node (ref "D11") (pin "4") (pinfunction "DIN_4") (pintype "input"))
      (node (ref "R25") (pin "1") (pinfunction "1_1") (pintype "passive"))
    )
    (net (code "92") (name "Net-(D11-DOUT)") (class "Default")
      (node (ref "D11") (pin "2") (pinfunction "DOUT_2") (pintype "output"))
      (node (ref "TP28") (pin "1") (pinfunction "TP_1") (pintype "passive"))
    )
    (net (code "93") (name "Net-(J2-GND)") (class "Default")
      (node (ref "FB6") (pin "1") (pinfunction "1_1") (pintype "passive"))
      (node (ref "J2") (pin "5") (pinfunction "GND_5") (pintype "passive"))
    )
    (net (code "94") (name "Net-(J2-Shield)") (class "Default")
      (node (ref "C30") (pin "2") (pinfunction "2_2") (pintype "passive"))
      (node (ref "J2") (pin "S") (pinfunction "Shield_S") (pintype "passive"))
      (node (ref "R22") (pin "2") (pinfunction "2_2") (pintype "passive"))
    )
    (net (code "95") (name "Net-(R6-Pad1)") (class "Default")
      (node (ref "R6") (pin "1") (pinfunction "1_1") (pintype "passive"))
      (node (ref "R7") (pin "2") (pinfunction "2_2") (pintype "passive"))
    )
    (net (code "96") (name "Net-(TP1-TP)") (class "Default")
      (node (ref "J1") (pin "1") (pinfunction "1_1") (pintype "passive"))
      (node (ref "RT1") (pin "1") (pinfunction "1_1") (pintype "passive"))
      (node (ref "TP1") (pin "1") (pinfunction "TP_1") (pintype "passive"))
    )
    (net (code "97") (name "Net-(TP23-TP)") (class "Default")
      (node (ref "BR1") (pin "4") (pinfunction "~_4") (pintype "passive"))
      (node (ref "C42") (pin "2") (pinfunction "2_2") (pintype "passive"))
      (node (ref "J1") (pin "2") (pinfunction "2_2") (pintype "passive"))
      (node (ref "R2") (pin "1") (pinfunction "1_1") (pintype "passive"))
      (node (ref "TP23") (pin "1") (pinfunction "TP_1") (pintype "passive"))
    )
    (net (code "98") (name "Net-(TP26-TP)") (class "Default")
      (node (ref "R44") (pin "2") (pinfunction "2_2") (pintype "passive"))
      (node (ref "TP26") (pin "1") (pinfunction "TP_1") (pintype "passive"))
      (node (ref "U3") (pin "CD1") (pinfunction "CD1_CD1") (pintype "passive"))
    )
    (net (code "99") (name "Net-(U1-COMP)") (class "Default")
      (node (ref "R3") (pin "1") (pinfunction "1_1") (pintype "passive"))
      (node (ref "U1") (pin "5") (pinfunction "COMP_5") (pintype "passive"))
    )
    (net (code "100") (name "unconnected-(J1-PadM)") (class "Default")
      (node (ref "J1") (pin "M") (pinfunction "M_M") (pintype "passive"))
    )
    (net (code "101") (name "unconnected-(J2-ID-Pad4)") (class "Default")
      (node (ref "J2") (pin "4") (pinfunction "ID_4") (pintype "passive+no_connect"))
    )
    (net (code "102") (name "unconnected-(J3-PadM)") (class "Default")
      (node (ref "J3") (pin "M") (pinfunction "M_M") (pintype "passive"))
    )
    (net (code "103") (name "unconnected-(J4-Pad7)") (class "Default")
      (node (ref "J4") (pin "7") (pinfunction "7_7") (pintype "passive+no_connect"))
    )
    (net (code "104") (name "unconnected-(ST1-H1-Pad1)") (class "Default")
      (node (ref "ST1") (pin "1") (pinfunction "H1_1") (pintype "passive"))
    )
    (net (code "105") (name "unconnected-(ST2-H1-Pad1)") (class "Default")
      (node (ref "ST2") (pin "1") (pinfunction "H1_1") (pintype "passive"))
    )
    (net (code "106") (name "unconnected-(ST3-H1-Pad1)") (class "Default")
      (node (ref "ST3") (pin "1") (pinfunction "H1_1") (pintype "passive"))
    )
    (net (code "107") (name "unconnected-(ST4-H1-Pad1)") (class "Default")
      (node (ref "ST4") (pin "1") (pinfunction "H1_1") (pintype "passive"))
    )
    (net (code "108") (name "unconnected-(U3-DAT2-Pad1)") (class "Default")
      (node (ref "U3") (pin "1") (pinfunction "DAT2_1") (pintype "passive+no_connect"))
    )
    (net (code "109") (name "unconnected-(U6-DNC-Pad7)") (class "Default")
      (node (ref "U6") (pin "7") (pinfunction "DNC_7") (pintype "passive+no_connect"))
    )
    (net (code "110") (name "unconnected-(U6-DUPLED-Pad26)") (class "Default")
      (node (ref "U6") (pin "26") (pinfunction "DUPLED_26") (pintype "passive+no_connect"))
    )
    (net (code "111") (name "unconnected-(U6-NC_1-Pad12)") (class "Default")
      (node (ref "U6") (pin "12") (pinfunction "NC_1_12") (pintype "passive+no_connect"))
    )
    (net (code "112") (name "unconnected-(U6-NC_2-Pad13)") (class "Default")
      (node (ref "U6") (pin "13") (pinfunction "NC_2_13") (pintype "passive+no_connect"))
    )
    (net (code "113") (name "unconnected-(U6-NC_3-Pad46)") (class "Default")
      (node (ref "U6") (pin "46") (pinfunction "NC_3_46") (pintype "passive+no_connect"))
    )
    (net (code "114") (name "unconnected-(U6-NC_4-Pad47)") (class "Default")
      (node (ref "U6") (pin "47") (pinfunction "NC_4_47") (pintype "passive+no_connect"))
    )
    (net (code "115") (name "unconnected-(U6-RSVD_1-Pad23)") (class "Default")
      (node (ref "U6") (pin "23") (pinfunction "RSVD_1_23") (pintype "passive+no_connect"))
    )
    (net (code "116") (name "unconnected-(U6-SPDLED-Pad24)") (class "Default")
      (node (ref "U6") (pin "24") (pinfunction "SPDLED_24") (pintype "passive+no_connect"))
    )
    (net (code "117") (name "unconnected-(U6-VBG-Pad18)") (class "Default")
      (node (ref "U6") (pin "18") (pinfunction "VBG_18") (pintype "passive+no_connect"))
    )
  )
)
